# backplane.net
KiCad netlist of a schematic drawn in EAGLE
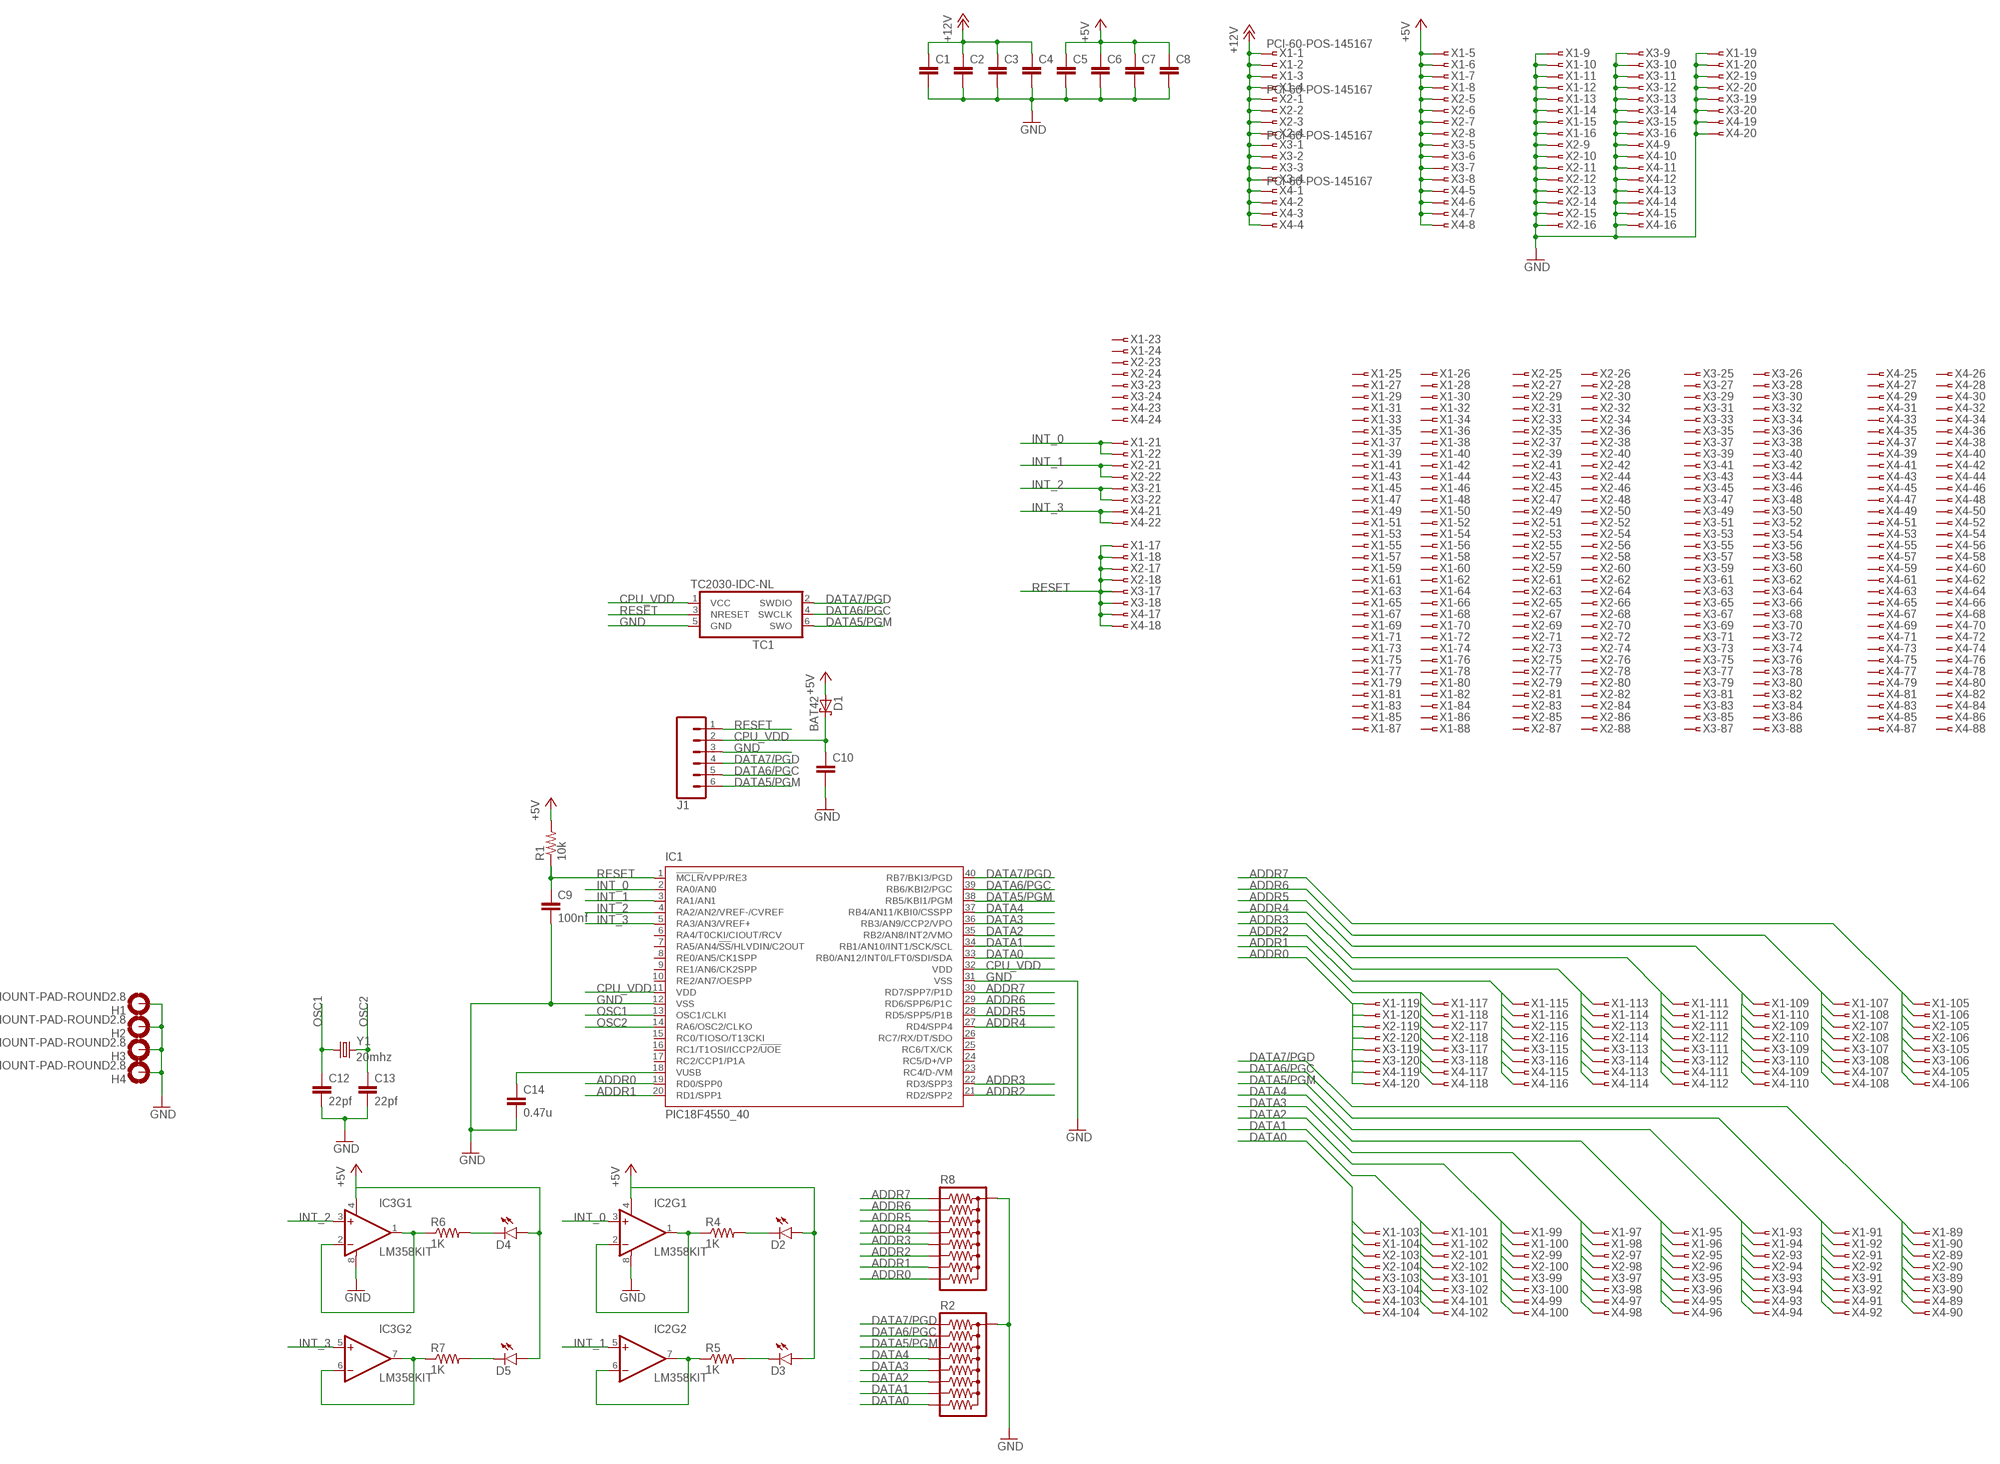
[diagram p0: schematic, sheet 1]

(export (version "E")
  (design (tool "Eeschema 10.0.6"))
  (components
    (comp (ref "C1")
      (value "0.1UF-50V-20%(PTH)KIT-EZ")
      (footprint "eagle-import:CAP-PTH-SMALL-KIT")
      (libsource (lib "eagle-import") (part "0.1UF-50V-20%(PTH)KIT-EZ"))
    )
    (comp (ref "C2")
      (value "0.1UF-50V-20%(PTH)KIT-EZ")
      (footprint "eagle-import:CAP-PTH-SMALL-KIT")
      (libsource (lib "eagle-import") (part "0.1UF-50V-20%(PTH)KIT-EZ"))
    )
    (comp (ref "C3")
      (value "0.1UF-50V-20%(PTH)KIT-EZ")
      (footprint "eagle-import:CAP-PTH-SMALL-KIT")
      (libsource (lib "eagle-import") (part "0.1UF-50V-20%(PTH)KIT-EZ"))
    )
    (comp (ref "C4")
      (value "0.1UF-50V-20%(PTH)KIT-EZ")
      (footprint "eagle-import:CAP-PTH-SMALL-KIT")
      (libsource (lib "eagle-import") (part "0.1UF-50V-20%(PTH)KIT-EZ"))
    )
    (comp (ref "C5")
      (value "0.1UF-50V-20%(PTH)KIT-EZ")
      (footprint "eagle-import:CAP-PTH-SMALL-KIT")
      (libsource (lib "eagle-import") (part "0.1UF-50V-20%(PTH)KIT-EZ"))
    )
    (comp (ref "C6")
      (value "0.1UF-50V-20%(PTH)KIT-EZ")
      (footprint "eagle-import:CAP-PTH-SMALL-KIT")
      (libsource (lib "eagle-import") (part "0.1UF-50V-20%(PTH)KIT-EZ"))
    )
    (comp (ref "C7")
      (value "0.1UF-50V-20%(PTH)KIT-EZ")
      (footprint "eagle-import:CAP-PTH-SMALL-KIT")
      (libsource (lib "eagle-import") (part "0.1UF-50V-20%(PTH)KIT-EZ"))
    )
    (comp (ref "C8")
      (value "0.1UF-50V-20%(PTH)KIT-EZ")
      (footprint "eagle-import:CAP-PTH-SMALL-KIT")
      (libsource (lib "eagle-import") (part "0.1UF-50V-20%(PTH)KIT-EZ"))
    )
    (comp (ref "C9")
      (value "100nf")
      (footprint "eagle-import:CAP-PTH-SMALL-KIT")
      (libsource (lib "eagle-import") (part "0.1UF-50V-20%(PTH)KIT-EZ"))
    )
    (comp (ref "C10")
      (value "0.1UF-50V-20%(PTH)KIT-EZ")
      (footprint "eagle-import:CAP-PTH-SMALL-KIT")
      (libsource (lib "eagle-import") (part "0.1UF-50V-20%(PTH)KIT-EZ"))
    )
    (comp (ref "C12")
      (value "22pf")
      (footprint "eagle-import:CAP-PTH-SMALL-KIT")
      (libsource (lib "eagle-import") (part "CAPKIT"))
    )
    (comp (ref "C13")
      (value "22pf")
      (footprint "eagle-import:CAP-PTH-SMALL-KIT")
      (libsource (lib "eagle-import") (part "CAPKIT"))
    )
    (comp (ref "C14")
      (value "0.47u")
      (footprint "eagle-import:CAP-PTH-SMALL-KIT")
      (libsource (lib "eagle-import") (part "CAPKIT"))
    )
    (comp (ref "D1")
      (value "BAT42")
      (footprint "eagle-import:DO35-10")
      (libsource (lib "eagle-import") (part "BAT42"))
    )
    (comp (ref "D2")
      (value "LED3MM")
      (footprint "eagle-import:LED3MM")
      (libsource (lib "eagle-import") (part "LED3MM"))
    )
    (comp (ref "D3")
      (value "LED3MM")
      (footprint "eagle-import:LED3MM")
      (libsource (lib "eagle-import") (part "LED3MM"))
    )
    (comp (ref "D4")
      (value "LED3MM")
      (footprint "eagle-import:LED3MM")
      (libsource (lib "eagle-import") (part "LED3MM"))
    )
    (comp (ref "D5")
      (value "LED3MM")
      (footprint "eagle-import:LED3MM")
      (libsource (lib "eagle-import") (part "LED3MM"))
    )
    (comp (ref "H1")
      (value "MOUNT-PAD-ROUND2.8")
      (footprint "eagle-import:2,8-PAD")
      (libsource (lib "eagle-import") (part "MOUNT-PAD-ROUND2.8"))
    )
    (comp (ref "H2")
      (value "MOUNT-PAD-ROUND2.8")
      (footprint "eagle-import:2,8-PAD")
      (libsource (lib "eagle-import") (part "MOUNT-PAD-ROUND2.8"))
    )
    (comp (ref "H3")
      (value "MOUNT-PAD-ROUND2.8")
      (footprint "eagle-import:2,8-PAD")
      (libsource (lib "eagle-import") (part "MOUNT-PAD-ROUND2.8"))
    )
    (comp (ref "H4")
      (value "MOUNT-PAD-ROUND2.8")
      (footprint "eagle-import:2,8-PAD")
      (libsource (lib "eagle-import") (part "MOUNT-PAD-ROUND2.8"))
    )
    (comp (ref "IC1")
      (value "PIC18F4550_40")
      (footprint "eagle-import:DIL40")
      (fields (field (name "MF") "MICROCHIP") (field (name "MPN") "PIC18F4550-I/P"))
      (libsource (lib "eagle-import") (part "PIC18F4_40550"))
    )
    (comp (ref "IC2")
      (value "LM358KIT")
      (footprint "eagle-import:DIP08-KIT")
      (libsource (lib "eagle-import") (part "LM358KIT"))
    )
    (comp (ref "IC3")
      (value "LM358KIT")
      (footprint "eagle-import:DIP08-KIT")
      (libsource (lib "eagle-import") (part "LM358KIT"))
    )
    (comp (ref "J1")
      (value "M06POLAR_LOCK")
      (footprint "eagle-import:MOLEX-1X6_LOCK")
      (libsource (lib "eagle-import") (part "M06POLAR_LOCK"))
    )
    (comp (ref "R1")
      (value "10k")
      (footprint "eagle-import:AXIAL-0.3EZ")
      (libsource (lib "eagle-import") (part "10KOHM-1/4W-1%(PTH)HORIZ-KIT"))
    )
    (comp (ref "R2")
      (value "RPACK-BUSSED-8-SIP-PTH-8")
      (footprint "eagle-import:RPACK-SIP-PTH-8")
      (libsource (lib "eagle-import") (part "RPACK-BUSSED-8-SIP-PTH-8"))
    )
    (comp (ref "R4")
      (value "1K")
      (footprint "eagle-import:AXIAL-0.1EZ")
      (libsource (lib "eagle-import") (part "1KOHM-1/4W-1%(PTH)VERT-KIT"))
    )
    (comp (ref "R5")
      (value "1K")
      (footprint "eagle-import:AXIAL-0.1EZ")
      (libsource (lib "eagle-import") (part "1KOHM-1/4W-1%(PTH)VERT-KIT"))
    )
    (comp (ref "R6")
      (value "1K")
      (footprint "eagle-import:AXIAL-0.1EZ")
      (libsource (lib "eagle-import") (part "1KOHM-1/4W-1%(PTH)VERT-KIT"))
    )
    (comp (ref "R7")
      (value "1K")
      (footprint "eagle-import:AXIAL-0.1EZ")
      (libsource (lib "eagle-import") (part "1KOHM-1/4W-1%(PTH)VERT-KIT"))
    )
    (comp (ref "R8")
      (value "RPACK-BUSSED-8-SIP-PTH-8")
      (footprint "eagle-import:RPACK-SIP-PTH-8")
      (libsource (lib "eagle-import") (part "RPACK-BUSSED-8-SIP-PTH-8"))
    )
    (comp (ref "TC1")
      (value "TC2030-IDC-NL")
      (footprint "eagle-import:TC2030-IDC-NL")
      (libsource (lib "eagle-import") (part "TC2030-IDC-NL"))
    )
    (comp (ref "X1")
      (value "PCI-60-POS-145167")
      (footprint "eagle-import:145167-2")
      (libsource (lib "eagle-import") (part "PCI-60-POS-145167"))
    )
    (comp (ref "X2")
      (value "PCI-60-POS-145167")
      (footprint "eagle-import:145167-2")
      (libsource (lib "eagle-import") (part "PCI-60-POS-145167"))
    )
    (comp (ref "X3")
      (value "PCI-60-POS-145167")
      (footprint "eagle-import:145167-2")
      (libsource (lib "eagle-import") (part "PCI-60-POS-145167"))
    )
    (comp (ref "X4")
      (value "PCI-60-POS-145167")
      (footprint "eagle-import:145167-2")
      (libsource (lib "eagle-import") (part "PCI-60-POS-145167"))
    )
    (comp (ref "Y1")
      (value "20mhz")
      (footprint "eagle-import:HC49U-V")
      (libsource (lib "eagle-import") (part "CRYSTALHC49UV"))
    )
  )
  (nets
    (net (code "1") (name "+5V") (class "Default")
      (node (ref "C5") (pin "1") (pinfunction "1_1") (pintype "passive"))
      (node (ref "C6") (pin "1") (pinfunction "1_1") (pintype "passive"))
      (node (ref "C7") (pin "1") (pinfunction "1_1") (pintype "passive"))
      (node (ref "C8") (pin "1") (pinfunction "1_1") (pintype "passive"))
      (node (ref "D1") (pin "A") (pinfunction "A_A") (pintype "passive"))
      (node (ref "D2") (pin "A") (pinfunction "A_A") (pintype "passive"))
      (node (ref "D3") (pin "A") (pinfunction "A_A") (pintype "passive"))
      (node (ref "D4") (pin "A") (pinfunction "A_A") (pintype "passive"))
      (node (ref "D5") (pin "A") (pinfunction "A_A") (pintype "passive"))
      (node (ref "IC2") (pin "4") (pinfunction "V-_4") (pintype "power_in"))
      (node (ref "IC3") (pin "4") (pinfunction "V-_4") (pintype "power_in"))
      (node (ref "R1") (pin "P$2") (pinfunction "2_P$2") (pintype "passive"))
      (node (ref "X1") (pin "5") (pinfunction "1_5") (pintype "passive"))
      (node (ref "X1") (pin "6") (pinfunction "1_6") (pintype "passive"))
      (node (ref "X1") (pin "7") (pinfunction "1_7") (pintype "passive"))
      (node (ref "X1") (pin "8") (pinfunction "1_8") (pintype "passive"))
      (node (ref "X2") (pin "5") (pinfunction "1_5") (pintype "passive"))
      (node (ref "X2") (pin "6") (pinfunction "1_6") (pintype "passive"))
      (node (ref "X2") (pin "7") (pinfunction "1_7") (pintype "passive"))
      (node (ref "X2") (pin "8") (pinfunction "1_8") (pintype "passive"))
      (node (ref "X3") (pin "5") (pinfunction "1_5") (pintype "passive"))
      (node (ref "X3") (pin "6") (pinfunction "1_6") (pintype "passive"))
      (node (ref "X3") (pin "7") (pinfunction "1_7") (pintype "passive"))
      (node (ref "X3") (pin "8") (pinfunction "1_8") (pintype "passive"))
      (node (ref "X4") (pin "5") (pinfunction "1_5") (pintype "passive"))
      (node (ref "X4") (pin "6") (pinfunction "1_6") (pintype "passive"))
      (node (ref "X4") (pin "7") (pinfunction "1_7") (pintype "passive"))
      (node (ref "X4") (pin "8") (pinfunction "1_8") (pintype "passive"))
    )
    (net (code "2") (name "+12V") (class "Default")
      (node (ref "C1") (pin "1") (pinfunction "1_1") (pintype "passive"))
      (node (ref "C2") (pin "1") (pinfunction "1_1") (pintype "passive"))
      (node (ref "C3") (pin "1") (pinfunction "1_1") (pintype "passive"))
      (node (ref "C4") (pin "1") (pinfunction "1_1") (pintype "passive"))
      (node (ref "X1") (pin "1") (pinfunction "1_1") (pintype "passive"))
      (node (ref "X1") (pin "2") (pinfunction "1_2") (pintype "passive"))
      (node (ref "X1") (pin "3") (pinfunction "1_3") (pintype "passive"))
      (node (ref "X1") (pin "4") (pinfunction "1_4") (pintype "passive"))
      (node (ref "X2") (pin "1") (pinfunction "1_1") (pintype "passive"))
      (node (ref "X2") (pin "2") (pinfunction "1_2") (pintype "passive"))
      (node (ref "X2") (pin "3") (pinfunction "1_3") (pintype "passive"))
      (node (ref "X2") (pin "4") (pinfunction "1_4") (pintype "passive"))
      (node (ref "X3") (pin "1") (pinfunction "1_1") (pintype "passive"))
      (node (ref "X3") (pin "2") (pinfunction "1_2") (pintype "passive"))
      (node (ref "X3") (pin "3") (pinfunction "1_3") (pintype "passive"))
      (node (ref "X3") (pin "4") (pinfunction "1_4") (pintype "passive"))
      (node (ref "X4") (pin "1") (pinfunction "1_1") (pintype "passive"))
      (node (ref "X4") (pin "2") (pinfunction "1_2") (pintype "passive"))
      (node (ref "X4") (pin "3") (pinfunction "1_3") (pintype "passive"))
      (node (ref "X4") (pin "4") (pinfunction "1_4") (pintype "passive"))
    )
    (net (code "3") (name "/ADDR0") (class "Default")
      (node (ref "IC1") (pin "19") (pinfunction "RD0/SPP0_19") (pintype "bidirectional"))
      (node (ref "R8") (pin "P$9") (pinfunction "9_P$9") (pintype "passive"))
      (node (ref "X1") (pin "119") (pinfunction "1_119") (pintype "passive"))
      (node (ref "X1") (pin "120") (pinfunction "1_120") (pintype "passive"))
      (node (ref "X2") (pin "119") (pinfunction "1_119") (pintype "passive"))
      (node (ref "X2") (pin "120") (pinfunction "1_120") (pintype "passive"))
      (node (ref "X3") (pin "119") (pinfunction "1_119") (pintype "passive"))
      (node (ref "X3") (pin "120") (pinfunction "1_120") (pintype "passive"))
      (node (ref "X4") (pin "119") (pinfunction "1_119") (pintype "passive"))
      (node (ref "X4") (pin "120") (pinfunction "1_120") (pintype "passive"))
    )
    (net (code "4") (name "/ADDR1") (class "Default")
      (node (ref "IC1") (pin "20") (pinfunction "RD1/SPP1_20") (pintype "bidirectional"))
      (node (ref "R8") (pin "P$8") (pinfunction "8_P$8") (pintype "passive"))
      (node (ref "X1") (pin "117") (pinfunction "1_117") (pintype "passive"))
      (node (ref "X1") (pin "118") (pinfunction "1_118") (pintype "passive"))
      (node (ref "X2") (pin "117") (pinfunction "1_117") (pintype "passive"))
      (node (ref "X2") (pin "118") (pinfunction "1_118") (pintype "passive"))
      (node (ref "X3") (pin "117") (pinfunction "1_117") (pintype "passive"))
      (node (ref "X3") (pin "118") (pinfunction "1_118") (pintype "passive"))
      (node (ref "X4") (pin "117") (pinfunction "1_117") (pintype "passive"))
      (node (ref "X4") (pin "118") (pinfunction "1_118") (pintype "passive"))
    )
    (net (code "5") (name "/ADDR2") (class "Default")
      (node (ref "IC1") (pin "21") (pinfunction "RD2/SPP2_21") (pintype "bidirectional"))
      (node (ref "R8") (pin "P$7") (pinfunction "7_P$7") (pintype "passive"))
      (node (ref "X1") (pin "115") (pinfunction "1_115") (pintype "passive"))
      (node (ref "X1") (pin "116") (pinfunction "1_116") (pintype "passive"))
      (node (ref "X2") (pin "115") (pinfunction "1_115") (pintype "passive"))
      (node (ref "X2") (pin "116") (pinfunction "1_116") (pintype "passive"))
      (node (ref "X3") (pin "115") (pinfunction "1_115") (pintype "passive"))
      (node (ref "X3") (pin "116") (pinfunction "1_116") (pintype "passive"))
      (node (ref "X4") (pin "115") (pinfunction "1_115") (pintype "passive"))
      (node (ref "X4") (pin "116") (pinfunction "1_116") (pintype "passive"))
    )
    (net (code "6") (name "/ADDR3") (class "Default")
      (node (ref "IC1") (pin "22") (pinfunction "RD3/SPP3_22") (pintype "bidirectional"))
      (node (ref "R8") (pin "P$6") (pinfunction "6_P$6") (pintype "passive"))
      (node (ref "X1") (pin "113") (pinfunction "1_113") (pintype "passive"))
      (node (ref "X1") (pin "114") (pinfunction "1_114") (pintype "passive"))
      (node (ref "X2") (pin "113") (pinfunction "1_113") (pintype "passive"))
      (node (ref "X2") (pin "114") (pinfunction "1_114") (pintype "passive"))
      (node (ref "X3") (pin "113") (pinfunction "1_113") (pintype "passive"))
      (node (ref "X3") (pin "114") (pinfunction "1_114") (pintype "passive"))
      (node (ref "X4") (pin "113") (pinfunction "1_113") (pintype "passive"))
      (node (ref "X4") (pin "114") (pinfunction "1_114") (pintype "passive"))
    )
    (net (code "7") (name "/ADDR4") (class "Default")
      (node (ref "IC1") (pin "27") (pinfunction "RD4/SPP4_27") (pintype "bidirectional"))
      (node (ref "R8") (pin "P$5") (pinfunction "5_P$5") (pintype "passive"))
      (node (ref "X1") (pin "111") (pinfunction "1_111") (pintype "passive"))
      (node (ref "X1") (pin "112") (pinfunction "1_112") (pintype "passive"))
      (node (ref "X2") (pin "111") (pinfunction "1_111") (pintype "passive"))
      (node (ref "X2") (pin "112") (pinfunction "1_112") (pintype "passive"))
      (node (ref "X3") (pin "111") (pinfunction "1_111") (pintype "passive"))
      (node (ref "X3") (pin "112") (pinfunction "1_112") (pintype "passive"))
      (node (ref "X4") (pin "111") (pinfunction "1_111") (pintype "passive"))
      (node (ref "X4") (pin "112") (pinfunction "1_112") (pintype "passive"))
    )
    (net (code "8") (name "/ADDR5") (class "Default")
      (node (ref "IC1") (pin "28") (pinfunction "RD5/SPP5/P1B_28") (pintype "bidirectional"))
      (node (ref "R8") (pin "P$4") (pinfunction "4_P$4") (pintype "passive"))
      (node (ref "X1") (pin "109") (pinfunction "1_109") (pintype "passive"))
      (node (ref "X1") (pin "110") (pinfunction "1_110") (pintype "passive"))
      (node (ref "X2") (pin "109") (pinfunction "1_109") (pintype "passive"))
      (node (ref "X2") (pin "110") (pinfunction "1_110") (pintype "passive"))
      (node (ref "X3") (pin "109") (pinfunction "1_109") (pintype "passive"))
      (node (ref "X3") (pin "110") (pinfunction "1_110") (pintype "passive"))
      (node (ref "X4") (pin "109") (pinfunction "1_109") (pintype "passive"))
      (node (ref "X4") (pin "110") (pinfunction "1_110") (pintype "passive"))
    )
    (net (code "9") (name "/ADDR6") (class "Default")
      (node (ref "IC1") (pin "29") (pinfunction "RD6/SPP6/P1C_29") (pintype "bidirectional"))
      (node (ref "R8") (pin "P$3") (pinfunction "3_P$3") (pintype "passive"))
      (node (ref "X1") (pin "107") (pinfunction "1_107") (pintype "passive"))
      (node (ref "X1") (pin "108") (pinfunction "1_108") (pintype "passive"))
      (node (ref "X2") (pin "107") (pinfunction "1_107") (pintype "passive"))
      (node (ref "X2") (pin "108") (pinfunction "1_108") (pintype "passive"))
      (node (ref "X3") (pin "107") (pinfunction "1_107") (pintype "passive"))
      (node (ref "X3") (pin "108") (pinfunction "1_108") (pintype "passive"))
      (node (ref "X4") (pin "107") (pinfunction "1_107") (pintype "passive"))
      (node (ref "X4") (pin "108") (pinfunction "1_108") (pintype "passive"))
    )
    (net (code "10") (name "/ADDR7") (class "Default")
      (node (ref "IC1") (pin "30") (pinfunction "RD7/SPP7/P1D_30") (pintype "bidirectional"))
      (node (ref "R8") (pin "P$2") (pinfunction "2_P$2") (pintype "passive"))
      (node (ref "X1") (pin "105") (pinfunction "1_105") (pintype "passive"))
      (node (ref "X1") (pin "106") (pinfunction "1_106") (pintype "passive"))
      (node (ref "X2") (pin "105") (pinfunction "1_105") (pintype "passive"))
      (node (ref "X2") (pin "106") (pinfunction "1_106") (pintype "passive"))
      (node (ref "X3") (pin "105") (pinfunction "1_105") (pintype "passive"))
      (node (ref "X3") (pin "106") (pinfunction "1_106") (pintype "passive"))
      (node (ref "X4") (pin "105") (pinfunction "1_105") (pintype "passive"))
      (node (ref "X4") (pin "106") (pinfunction "1_106") (pintype "passive"))
    )
    (net (code "11") (name "/CPU_VDD") (class "Default")
      (node (ref "C10") (pin "1") (pinfunction "1_1") (pintype "passive"))
      (node (ref "D1") (pin "C") (pinfunction "C_C") (pintype "passive"))
      (node (ref "IC1") (pin "11") (pinfunction "VDD_11") (pintype "power_in"))
      (node (ref "IC1") (pin "32") (pinfunction "VDD_32") (pintype "power_in"))
      (node (ref "J1") (pin "2") (pinfunction "2_2") (pintype "passive"))
      (node (ref "TC1") (pin "1") (pinfunction "VCC_1") (pintype "passive"))
    )
    (net (code "12") (name "/DATA0") (class "Default")
      (node (ref "IC1") (pin "33") (pinfunction "RB0/AN12/INT0/LFT0/SDI/SDA_33") (pintype "bidirectional"))
      (node (ref "R2") (pin "P$9") (pinfunction "9_P$9") (pintype "passive"))
      (node (ref "X1") (pin "103") (pinfunction "1_103") (pintype "passive"))
      (node (ref "X1") (pin "104") (pinfunction "1_104") (pintype "passive"))
      (node (ref "X2") (pin "103") (pinfunction "1_103") (pintype "passive"))
      (node (ref "X2") (pin "104") (pinfunction "1_104") (pintype "passive"))
      (node (ref "X3") (pin "103") (pinfunction "1_103") (pintype "passive"))
      (node (ref "X3") (pin "104") (pinfunction "1_104") (pintype "passive"))
      (node (ref "X4") (pin "103") (pinfunction "1_103") (pintype "passive"))
      (node (ref "X4") (pin "104") (pinfunction "1_104") (pintype "passive"))
    )
    (net (code "13") (name "/DATA1") (class "Default")
      (node (ref "IC1") (pin "34") (pinfunction "RB1/AN10/INT1/SCK/SCL_34") (pintype "bidirectional"))
      (node (ref "R2") (pin "P$8") (pinfunction "8_P$8") (pintype "passive"))
      (node (ref "X1") (pin "101") (pinfunction "1_101") (pintype "passive"))
      (node (ref "X1") (pin "102") (pinfunction "1_102") (pintype "passive"))
      (node (ref "X2") (pin "101") (pinfunction "1_101") (pintype "passive"))
      (node (ref "X2") (pin "102") (pinfunction "1_102") (pintype "passive"))
      (node (ref "X3") (pin "101") (pinfunction "1_101") (pintype "passive"))
      (node (ref "X3") (pin "102") (pinfunction "1_102") (pintype "passive"))
      (node (ref "X4") (pin "101") (pinfunction "1_101") (pintype "passive"))
      (node (ref "X4") (pin "102") (pinfunction "1_102") (pintype "passive"))
    )
    (net (code "14") (name "/DATA2") (class "Default")
      (node (ref "IC1") (pin "35") (pinfunction "RB2/AN8/INT2/VMO_35") (pintype "bidirectional"))
      (node (ref "R2") (pin "P$7") (pinfunction "7_P$7") (pintype "passive"))
      (node (ref "X1") (pin "100") (pinfunction "1_100") (pintype "passive"))
      (node (ref "X1") (pin "99") (pinfunction "1_99") (pintype "passive"))
      (node (ref "X2") (pin "100") (pinfunction "1_100") (pintype "passive"))
      (node (ref "X2") (pin "99") (pinfunction "1_99") (pintype "passive"))
      (node (ref "X3") (pin "100") (pinfunction "1_100") (pintype "passive"))
      (node (ref "X3") (pin "99") (pinfunction "1_99") (pintype "passive"))
      (node (ref "X4") (pin "100") (pinfunction "1_100") (pintype "passive"))
      (node (ref "X4") (pin "99") (pinfunction "1_99") (pintype "passive"))
    )
    (net (code "15") (name "/DATA3") (class "Default")
      (node (ref "IC1") (pin "36") (pinfunction "RB3/AN9/CCP2/VPO_36") (pintype "bidirectional"))
      (node (ref "R2") (pin "P$6") (pinfunction "6_P$6") (pintype "passive"))
      (node (ref "X1") (pin "97") (pinfunction "1_97") (pintype "passive"))
      (node (ref "X1") (pin "98") (pinfunction "1_98") (pintype "passive"))
      (node (ref "X2") (pin "97") (pinfunction "1_97") (pintype "passive"))
      (node (ref "X2") (pin "98") (pinfunction "1_98") (pintype "passive"))
      (node (ref "X3") (pin "97") (pinfunction "1_97") (pintype "passive"))
      (node (ref "X3") (pin "98") (pinfunction "1_98") (pintype "passive"))
      (node (ref "X4") (pin "97") (pinfunction "1_97") (pintype "passive"))
      (node (ref "X4") (pin "98") (pinfunction "1_98") (pintype "passive"))
    )
    (net (code "16") (name "/DATA4") (class "Default")
      (node (ref "IC1") (pin "37") (pinfunction "RB4/AN11/KBI0/CSSPP_37") (pintype "bidirectional"))
      (node (ref "R2") (pin "P$5") (pinfunction "5_P$5") (pintype "passive"))
      (node (ref "X1") (pin "95") (pinfunction "1_95") (pintype "passive"))
      (node (ref "X1") (pin "96") (pinfunction "1_96") (pintype "passive"))
      (node (ref "X2") (pin "95") (pinfunction "1_95") (pintype "passive"))
      (node (ref "X2") (pin "96") (pinfunction "1_96") (pintype "passive"))
      (node (ref "X3") (pin "95") (pinfunction "1_95") (pintype "passive"))
      (node (ref "X3") (pin "96") (pinfunction "1_96") (pintype "passive"))
      (node (ref "X4") (pin "95") (pinfunction "1_95") (pintype "passive"))
      (node (ref "X4") (pin "96") (pinfunction "1_96") (pintype "passive"))
    )
    (net (code "17") (name "/DATA5{slash}PGM") (class "Default")
      (node (ref "IC1") (pin "38") (pinfunction "RB5/KBI1/PGM_38") (pintype "bidirectional"))
      (node (ref "J1") (pin "6") (pinfunction "6_6") (pintype "passive"))
      (node (ref "R2") (pin "P$4") (pinfunction "4_P$4") (pintype "passive"))
      (node (ref "TC1") (pin "6") (pinfunction "SWO_6") (pintype "passive"))
      (node (ref "X1") (pin "93") (pinfunction "1_93") (pintype "passive"))
      (node (ref "X1") (pin "94") (pinfunction "1_94") (pintype "passive"))
      (node (ref "X2") (pin "93") (pinfunction "1_93") (pintype "passive"))
      (node (ref "X2") (pin "94") (pinfunction "1_94") (pintype "passive"))
      (node (ref "X3") (pin "93") (pinfunction "1_93") (pintype "passive"))
      (node (ref "X3") (pin "94") (pinfunction "1_94") (pintype "passive"))
      (node (ref "X4") (pin "93") (pinfunction "1_93") (pintype "passive"))
      (node (ref "X4") (pin "94") (pinfunction "1_94") (pintype "passive"))
    )
    (net (code "18") (name "/DATA6{slash}PGC") (class "Default")
      (node (ref "IC1") (pin "39") (pinfunction "RB6/KBI2/PGC_39") (pintype "bidirectional"))
      (node (ref "J1") (pin "5") (pinfunction "5_5") (pintype "passive"))
      (node (ref "R2") (pin "P$3") (pinfunction "3_P$3") (pintype "passive"))
      (node (ref "TC1") (pin "4") (pinfunction "SWCLK_4") (pintype "passive"))
      (node (ref "X1") (pin "91") (pinfunction "1_91") (pintype "passive"))
      (node (ref "X1") (pin "92") (pinfunction "1_92") (pintype "passive"))
      (node (ref "X2") (pin "91") (pinfunction "1_91") (pintype "passive"))
      (node (ref "X2") (pin "92") (pinfunction "1_92") (pintype "passive"))
      (node (ref "X3") (pin "91") (pinfunction "1_91") (pintype "passive"))
      (node (ref "X3") (pin "92") (pinfunction "1_92") (pintype "passive"))
      (node (ref "X4") (pin "91") (pinfunction "1_91") (pintype "passive"))
      (node (ref "X4") (pin "92") (pinfunction "1_92") (pintype "passive"))
    )
    (net (code "19") (name "/DATA7{slash}PGD") (class "Default")
      (node (ref "IC1") (pin "40") (pinfunction "RB7/BKI3/PGD_40") (pintype "bidirectional"))
      (node (ref "J1") (pin "4") (pinfunction "4_4") (pintype "passive"))
      (node (ref "R2") (pin "P$2") (pinfunction "2_P$2") (pintype "passive"))
      (node (ref "TC1") (pin "2") (pinfunction "SWDIO_2") (pintype "passive"))
      (node (ref "X1") (pin "89") (pinfunction "1_89") (pintype "passive"))
      (node (ref "X1") (pin "90") (pinfunction "1_90") (pintype "passive"))
      (node (ref "X2") (pin "89") (pinfunction "1_89") (pintype "passive"))
      (node (ref "X2") (pin "90") (pinfunction "1_90") (pintype "passive"))
      (node (ref "X3") (pin "89") (pinfunction "1_89") (pintype "passive"))
      (node (ref "X3") (pin "90") (pinfunction "1_90") (pintype "passive"))
      (node (ref "X4") (pin "89") (pinfunction "1_89") (pintype "passive"))
      (node (ref "X4") (pin "90") (pinfunction "1_90") (pintype "passive"))
    )
    (net (code "20") (name "/INT_0") (class "Default")
      (node (ref "IC1") (pin "2") (pinfunction "RA0/AN0_2") (pintype "bidirectional"))
      (node (ref "IC2") (pin "3") (pinfunction "+IN_3") (pintype "input"))
      (node (ref "X1") (pin "21") (pinfunction "1_21") (pintype "passive"))
      (node (ref "X1") (pin "22") (pinfunction "1_22") (pintype "passive"))
    )
    (net (code "21") (name "/INT_1") (class "Default")
      (node (ref "IC1") (pin "3") (pinfunction "RA1/AN1_3") (pintype "bidirectional"))
      (node (ref "IC2") (pin "5") (pinfunction "+IN_5") (pintype "input"))
      (node (ref "X2") (pin "21") (pinfunction "1_21") (pintype "passive"))
      (node (ref "X2") (pin "22") (pinfunction "1_22") (pintype "passive"))
    )
    (net (code "22") (name "/INT_2") (class "Default")
      (node (ref "IC1") (pin "4") (pinfunction "RA2/AN2/VREF-/CVREF_4") (pintype "bidirectional"))
      (node (ref "IC3") (pin "3") (pinfunction "+IN_3") (pintype "input"))
      (node (ref "X3") (pin "21") (pinfunction "1_21") (pintype "passive"))
      (node (ref "X3") (pin "22") (pinfunction "1_22") (pintype "passive"))
    )
    (net (code "23") (name "/INT_3") (class "Default")
      (node (ref "IC1") (pin "5") (pinfunction "RA3/AN3/VREF+_5") (pintype "bidirectional"))
      (node (ref "IC3") (pin "5") (pinfunction "+IN_5") (pintype "input"))
      (node (ref "X4") (pin "21") (pinfunction "1_21") (pintype "passive"))
      (node (ref "X4") (pin "22") (pinfunction "1_22") (pintype "passive"))
    )
    (net (code "24") (name "/OSC1") (class "Default")
      (node (ref "C12") (pin "1") (pinfunction "1_1") (pintype "passive"))
      (node (ref "IC1") (pin "13") (pinfunction "OSC1/CLKI_13") (pintype "input"))
      (node (ref "Y1") (pin "1") (pinfunction "1_1") (pintype "passive"))
    )
    (net (code "25") (name "/OSC2") (class "Default")
      (node (ref "C13") (pin "1") (pinfunction "1_1") (pintype "passive"))
      (node (ref "IC1") (pin "14") (pinfunction "RA6/OSC2/CLKO_14") (pintype "output"))
      (node (ref "Y1") (pin "2") (pinfunction "2_2") (pintype "passive"))
    )
    (net (code "26") (name "/RESET") (class "Default")
      (node (ref "C9") (pin "1") (pinfunction "1_1") (pintype "passive"))
      (node (ref "IC1") (pin "1") (pinfunction "~{MCLR}/VPP/RE3_1") (pintype "input"))
      (node (ref "J1") (pin "1") (pinfunction "1_1") (pintype "passive"))
      (node (ref "R1") (pin "P$1") (pinfunction "1_P$1") (pintype "passive"))
      (node (ref "TC1") (pin "3") (pinfunction "NRESET_3") (pintype "passive"))
      (node (ref "X1") (pin "17") (pinfunction "1_17") (pintype "passive"))
      (node (ref "X1") (pin "18") (pinfunction "1_18") (pintype "passive"))
      (node (ref "X2") (pin "17") (pinfunction "1_17") (pintype "passive"))
      (node (ref "X2") (pin "18") (pinfunction "1_18") (pintype "passive"))
      (node (ref "X3") (pin "17") (pinfunction "1_17") (pintype "passive"))
      (node (ref "X3") (pin "18") (pinfunction "1_18") (pintype "passive"))
      (node (ref "X4") (pin "17") (pinfunction "1_17") (pintype "passive"))
      (node (ref "X4") (pin "18") (pinfunction "1_18") (pintype "passive"))
    )
    (net (code "27") (name "GND") (class "Default")
      (node (ref "C1") (pin "2") (pinfunction "2_2") (pintype "passive"))
      (node (ref "C10") (pin "2") (pinfunction "2_2") (pintype "passive"))
      (node (ref "C12") (pin "2") (pinfunction "2_2") (pintype "passive"))
      (node (ref "C13") (pin "2") (pinfunction "2_2") (pintype "passive"))
      (node (ref "C14") (pin "2") (pinfunction "2_2") (pintype "passive"))
      (node (ref "C2") (pin "2") (pinfunction "2_2") (pintype "passive"))
      (node (ref "C3") (pin "2") (pinfunction "2_2") (pintype "passive"))
      (node (ref "C4") (pin "2") (pinfunction "2_2") (pintype "passive"))
      (node (ref "C5") (pin "2") (pinfunction "2_2") (pintype "passive"))
      (node (ref "C6") (pin "2") (pinfunction "2_2") (pintype "passive"))
      (node (ref "C7") (pin "2") (pinfunction "2_2") (pintype "passive"))
      (node (ref "C8") (pin "2") (pinfunction "2_2") (pintype "passive"))
      (node (ref "C9") (pin "2") (pinfunction "2_2") (pintype "passive"))
      (node (ref "H1") (pin "B2,8") (pinfunction "MOUNT_B2,8") (pintype "passive"))
      (node (ref "H2") (pin "B2,8") (pinfunction "MOUNT_B2,8") (pintype "passive"))
      (node (ref "H3") (pin "B2,8") (pinfunction "MOUNT_B2,8") (pintype "passive"))
      (node (ref "H4") (pin "B2,8") (pinfunction "MOUNT_B2,8") (pintype "passive"))
      (node (ref "IC1") (pin "12") (pinfunction "VSS_12") (pintype "power_in"))
      (node (ref "IC1") (pin "31") (pinfunction "VSS_31") (pintype "power_in"))
      (node (ref "IC2") (pin "8") (pinfunction "V+_8") (pintype "power_in"))
      (node (ref "IC3") (pin "8") (pinfunction "V+_8") (pintype "power_in"))
      (node (ref "J1") (pin "3") (pinfunction "3_3") (pintype "passive"))
      (node (ref "R2") (pin "P$1") (pinfunction "1_P$1") (pintype "passive"))
      (node (ref "R8") (pin "P$1") (pinfunction "1_P$1") (pintype "passive"))
      (node (ref "TC1") (pin "5") (pinfunction "GND_5") (pintype "passive"))
      (node (ref "X1") (pin "10") (pinfunction "1_10") (pintype "passive"))
      (node (ref "X1") (pin "11") (pinfunction "1_11") (pintype "passive"))
      (node (ref "X1") (pin "12") (pinfunction "1_12") (pintype "passive"))
      (node (ref "X1") (pin "13") (pinfunction "1_13") (pintype "passive"))
      (node (ref "X1") (pin "14") (pinfunction "1_14") (pintype "passive"))
      (node (ref "X1") (pin "15") (pinfunction "1_15") (pintype "passive"))
      (node (ref "X1") (pin "16") (pinfunction "1_16") (pintype "passive"))
      (node (ref "X1") (pin "19") (pinfunction "1_19") (pintype "passive"))
      (node (ref "X1") (pin "20") (pinfunction "1_20") (pintype "passive"))
      (node (ref "X1") (pin "9") (pinfunction "1_9") (pintype "passive"))
      (node (ref "X2") (pin "10") (pinfunction "1_10") (pintype "passive"))
      (node (ref "X2") (pin "11") (pinfunction "1_11") (pintype "passive"))
      (node (ref "X2") (pin "12") (pinfunction "1_12") (pintype "passive"))
      (node (ref "X2") (pin "13") (pinfunction "1_13") (pintype "passive"))
      (node (ref "X2") (pin "14") (pinfunction "1_14") (pintype "passive"))
      (node (ref "X2") (pin "15") (pinfunction "1_15") (pintype "passive"))
      (node (ref "X2") (pin "16") (pinfunction "1_16") (pintype "passive"))
      (node (ref "X2") (pin "19") (pinfunction "1_19") (pintype "passive"))
      (node (ref "X2") (pin "20") (pinfunction "1_20") (pintype "passive"))
      (node (ref "X2") (pin "9") (pinfunction "1_9") (pintype "passive"))
      (node (ref "X3") (pin "10") (pinfunction "1_10") (pintype "passive"))
      (node (ref "X3") (pin "11") (pinfunction "1_11") (pintype "passive"))
      (node (ref "X3") (pin "12") (pinfunction "1_12") (pintype "passive"))
      (node (ref "X3") (pin "13") (pinfunction "1_13") (pintype "passive"))
      (node (ref "X3") (pin "14") (pinfunction "1_14") (pintype "passive"))
      (node (ref "X3") (pin "15") (pinfunction "1_15") (pintype "passive"))
      (node (ref "X3") (pin "16") (pinfunction "1_16") (pintype "passive"))
      (node (ref "X3") (pin "19") (pinfunction "1_19") (pintype "passive"))
      (node (ref "X3") (pin "20") (pinfunction "1_20") (pintype "passive"))
      (node (ref "X3") (pin "9") (pinfunction "1_9") (pintype "passive"))
      (node (ref "X4") (pin "10") (pinfunction "1_10") (pintype "passive"))
      (node (ref "X4") (pin "11") (pinfunction "1_11") (pintype "passive"))
      (node (ref "X4") (pin "12") (pinfunction "1_12") (pintype "passive"))
      (node (ref "X4") (pin "13") (pinfunction "1_13") (pintype "passive"))
      (node (ref "X4") (pin "14") (pinfunction "1_14") (pintype "passive"))
      (node (ref "X4") (pin "15") (pinfunction "1_15") (pintype "passive"))
      (node (ref "X4") (pin "16") (pinfunction "1_16") (pintype "passive"))
      (node (ref "X4") (pin "19") (pinfunction "1_19") (pintype "passive"))
      (node (ref "X4") (pin "20") (pinfunction "1_20") (pintype "passive"))
      (node (ref "X4") (pin "9") (pinfunction "1_9") (pintype "passive"))
    )
    (net (code "28") (name "Net-(D2-C)") (class "Default")
      (node (ref "D2") (pin "K") (pinfunction "C_K") (pintype "passive"))
      (node (ref "R4") (pin "P$2") (pinfunction "2_P$2") (pintype "passive"))
    )
    (net (code "29") (name "Net-(D3-C)") (class "Default")
      (node (ref "D3") (pin "K") (pinfunction "C_K") (pintype "passive"))
      (node (ref "R5") (pin "P$2") (pinfunction "2_P$2") (pintype "passive"))
    )
    (net (code "30") (name "Net-(D4-C)") (class "Default")
      (node (ref "D4") (pin "K") (pinfunction "C_K") (pintype "passive"))
      (node (ref "R6") (pin "P$2") (pinfunction "2_P$2") (pintype "passive"))
    )
    (net (code "31") (name "Net-(D5-C)") (class "Default")
      (node (ref "D5") (pin "K") (pinfunction "C_K") (pintype "passive"))
      (node (ref "R7") (pin "P$2") (pinfunction "2_P$2") (pintype "passive"))
    )
    (net (code "32") (name "Net-(IC1-VUSB)") (class "Default")
      (node (ref "C14") (pin "1") (pinfunction "1_1") (pintype "passive"))
      (node (ref "IC1") (pin "18") (pinfunction "VUSB_18") (pintype "bidirectional"))
    )
    (net (code "33") (name "Net-(IC2A--IN)") (class "Default")
      (node (ref "IC2") (pin "1") (pinfunction "OUT_1") (pintype "output"))
      (node (ref "IC2") (pin "2") (pinfunction "-IN_2") (pintype "input"))
      (node (ref "R4") (pin "P$1") (pinfunction "1_P$1") (pintype "passive"))
    )
    (net (code "34") (name "Net-(IC2B--IN)") (class "Default")
      (node (ref "IC2") (pin "6") (pinfunction "-IN_6") (pintype "input"))
      (node (ref "IC2") (pin "7") (pinfunction "OUT_7") (pintype "output"))
      (node (ref "R5") (pin "P$1") (pinfunction "1_P$1") (pintype "passive"))
    )
    (net (code "35") (name "Net-(IC3A--IN)") (class "Default")
      (node (ref "IC3") (pin "1") (pinfunction "OUT_1") (pintype "output"))
      (node (ref "IC3") (pin "2") (pinfunction "-IN_2") (pintype "input"))
      (node (ref "R6") (pin "P$1") (pinfunction "1_P$1") (pintype "passive"))
    )
    (net (code "36") (name "Net-(IC3B--IN)") (class "Default")
      (node (ref "IC3") (pin "6") (pinfunction "-IN_6") (pintype "input"))
      (node (ref "IC3") (pin "7") (pinfunction "OUT_7") (pintype "output"))
      (node (ref "R7") (pin "P$1") (pinfunction "1_P$1") (pintype "passive"))
    )
    (net (code "37") (name "unconnected-(IC1-RA4{slash}T0CKI{slash}CIOUT{slash}RCV-Pad6)") (class "Default")
      (node (ref "IC1") (pin "6") (pinfunction "RA4/T0CKI/CIOUT/RCV_6") (pintype "bidirectional"))
    )
    (net (code "38") (name "unconnected-(IC1-RA5{slash}AN4{slash}~{SS}{slash}HLVDIN{slash}C2OUT-Pad7)") (class "Default")
      (node (ref "IC1") (pin "7") (pinfunction "RA5/AN4/~{SS}/HLVDIN/C2OUT_7") (pintype "bidirectional"))
    )
    (net (code "39") (name "unconnected-(IC1-RC0{slash}TIOSO{slash}T13CKI-Pad15)") (class "Default")
      (node (ref "IC1") (pin "15") (pinfunction "RC0/TIOSO/T13CKI_15") (pintype "bidirectional"))
    )
    (net (code "40") (name "unconnected-(IC1-RC1{slash}T1OSI{slash}ICCP2{slash}~{UOE}-Pad16)") (class "Default")
      (node (ref "IC1") (pin "16") (pinfunction "RC1/T1OSI/ICCP2/~{UOE}_16") (pintype "bidirectional"))
    )
    (net (code "41") (name "unconnected-(IC1-RC2{slash}CCP1{slash}P1A-Pad17)") (class "Default")
      (node (ref "IC1") (pin "17") (pinfunction "RC2/CCP1/P1A_17") (pintype "bidirectional"))
    )
    (net (code "42") (name "unconnected-(IC1-RC4{slash}D-{slash}VM-Pad23)") (class "Default")
      (node (ref "IC1") (pin "23") (pinfunction "RC4/D-/VM_23") (pintype "bidirectional"))
    )
    (net (code "43") (name "unconnected-(IC1-RC5{slash}D+{slash}VP-Pad24)") (class "Default")
      (node (ref "IC1") (pin "24") (pinfunction "RC5/D+/VP_24") (pintype "bidirectional"))
    )
    (net (code "44") (name "unconnected-(IC1-RC6{slash}TX{slash}CK-Pad25)") (class "Default")
      (node (ref "IC1") (pin "25") (pinfunction "RC6/TX/CK_25") (pintype "bidirectional"))
    )
    (net (code "45") (name "unconnected-(IC1-RC7{slash}RX{slash}DT{slash}SDO-Pad26)") (class "Default")
      (node (ref "IC1") (pin "26") (pinfunction "RC7/RX/DT/SDO_26") (pintype "bidirectional"))
    )
    (net (code "46") (name "unconnected-(IC1-RE0{slash}AN5{slash}CK1SPP-Pad8)") (class "Default")
      (node (ref "IC1") (pin "8") (pinfunction "RE0/AN5/CK1SPP_8") (pintype "bidirectional"))
    )
    (net (code "47") (name "unconnected-(IC1-RE1{slash}AN6{slash}CK2SPP-Pad9)") (class "Default")
      (node (ref "IC1") (pin "9") (pinfunction "RE1/AN6/CK2SPP_9") (pintype "bidirectional"))
    )
    (net (code "48") (name "unconnected-(IC1-RE2{slash}AN7{slash}OESPP-Pad10)") (class "Default")
      (node (ref "IC1") (pin "10") (pinfunction "RE2/AN7/OESPP_10") (pintype "bidirectional"))
    )
    (net (code "49") (name "unconnected-(X1AK-1-Pad23)") (class "Default")
      (node (ref "X1") (pin "23") (pinfunction "1_23") (pintype "passive"))
    )
    (net (code "50") (name "unconnected-(X1AL-1-Pad24)") (class "Default")
      (node (ref "X1") (pin "24") (pinfunction "1_24") (pintype "passive"))
    )
    (net (code "51") (name "unconnected-(X1AM-1-Pad25)") (class "Default")
      (node (ref "X1") (pin "25") (pinfunction "1_25") (pintype "passive"))
    )
    (net (code "52") (name "unconnected-(X1AN-1-Pad26)") (class "Default")
      (node (ref "X1") (pin "26") (pinfunction "1_26") (pintype "passive"))
    )
    (net (code "53") (name "unconnected-(X1AO-1-Pad27)") (class "Default")
      (node (ref "X1") (pin "27") (pinfunction "1_27") (pintype "passive"))
    )
    (net (code "54") (name "unconnected-(X1AP-1-Pad28)") (class "Default")
      (node (ref "X1") (pin "28") (pinfunction "1_28") (pintype "passive"))
    )
    (net (code "55") (name "unconnected-(X1AQ-1-Pad29)") (class "Default")
      (node (ref "X1") (pin "29") (pinfunction "1_29") (pintype "passive"))
    )
    (net (code "56") (name "unconnected-(X1AS-1-Pad30)") (class "Default")
      (node (ref "X1") (pin "30") (pinfunction "1_30") (pintype "passive"))
    )
    (net (code "57") (name "unconnected-(X1AT-1-Pad31)") (class "Default")
      (node (ref "X1") (pin "31") (pinfunction "1_31") (pintype "passive"))
    )
    (net (code "58") (name "unconnected-(X1AU-1-Pad32)") (class "Default")
      (node (ref "X1") (pin "32") (pinfunction "1_32") (pintype "passive"))
    )
    (net (code "59") (name "unconnected-(X1AV-1-Pad33)") (class "Default")
      (node (ref "X1") (pin "33") (pinfunction "1_33") (pintype "passive"))
    )
    (net (code "60") (name "unconnected-(X1AW-1-Pad34)") (class "Default")
      (node (ref "X1") (pin "34") (pinfunction "1_34") (pintype "passive"))
    )
    (net (code "61") (name "unconnected-(X1AX-1-Pad35)") (class "Default")
      (node (ref "X1") (pin "35") (pinfunction "1_35") (pintype "passive"))
    )
    (net (code "62") (name "unconnected-(X1AY-1-Pad36)") (class "Default")
      (node (ref "X1") (pin "36") (pinfunction "1_36") (pintype "passive"))
    )
    (net (code "63") (name "unconnected-(X1AZ-1-Pad37)") (class "Default")
      (node (ref "X1") (pin "37") (pinfunction "1_37") (pintype "passive"))
    )
    (net (code "64") (name "unconnected-(X1BA-1-Pad38)") (class "Default")
      (node (ref "X1") (pin "38") (pinfunction "1_38") (pintype "passive"))
    )
    (net (code "65") (name "unconnected-(X1BB-1-Pad39)") (class "Default")
      (node (ref "X1") (pin "39") (pinfunction "1_39") (pintype "passive"))
    )
    (net (code "66") (name "unconnected-(X1BD-1-Pad40)") (class "Default")
      (node (ref "X1") (pin "40") (pinfunction "1_40") (pintype "passive"))
    )
    (net (code "67") (name "unconnected-(X1BE-1-Pad41)") (class "Default")
      (node (ref "X1") (pin "41") (pinfunction "1_41") (pintype "passive"))
    )
    (net (code "68") (name "unconnected-(X1BF-1-Pad42)") (class "Default")
      (node (ref "X1") (pin "42") (pinfunction "1_42") (pintype "passive"))
    )
    (net (code "69") (name "unconnected-(X1BG-1-Pad43)") (class "Default")
      (node (ref "X1") (pin "43") (pinfunction "1_43") (pintype "passive"))
    )
    (net (code "70") (name "unconnected-(X1BH-1-Pad44)") (class "Default")
      (node (ref "X1") (pin "44") (pinfunction "1_44") (pintype "passive"))
    )
    (net (code "71") (name "unconnected-(X1BI-1-Pad45)") (class "Default")
      (node (ref "X1") (pin "45") (pinfunction "1_45") (pintype "passive"))
    )
    (net (code "72") (name "unconnected-(X1BJ-1-Pad46)") (class "Default")
      (node (ref "X1") (pin "46") (pinfunction "1_46") (pintype "passive"))
    )
    (net (code "73") (name "unconnected-(X1BK-1-Pad47)") (class "Default")
      (node (ref "X1") (pin "47") (pinfunction "1_47") (pintype "passive"))
    )
    (net (code "74") (name "unconnected-(X1BL-1-Pad48)") (class "Default")
      (node (ref "X1") (pin "48") (pinfunction "1_48") (pintype "passive"))
    )
    (net (code "75") (name "unconnected-(X1BM-1-Pad49)") (class "Default")
      (node (ref "X1") (pin "49") (pinfunction "1_49") (pintype "passive"))
    )
    (net (code "76") (name "unconnected-(X1BO-1-Pad50)") (class "Default")
      (node (ref "X1") (pin "50") (pinfunction "1_50") (pintype "passive"))
    )
    (net (code "77") (name "unconnected-(X1BP-1-Pad51)") (class "Default")
      (node (ref "X1") (pin "51") (pinfunction "1_51") (pintype "passive"))
    )
    (net (code "78") (name "unconnected-(X1BQ-1-Pad52)") (class "Default")
      (node (ref "X1") (pin "52") (pinfunction "1_52") (pintype "passive"))
    )
    (net (code "79") (name "unconnected-(X1BR-1-Pad53)") (class "Default")
      (node (ref "X1") (pin "53") (pinfunction "1_53") (pintype "passive"))
    )
    (net (code "80") (name "unconnected-(X1BS-1-Pad54)") (class "Default")
      (node (ref "X1") (pin "54") (pinfunction "1_54") (pintype "passive"))
    )
    (net (code "81") (name "unconnected-(X1BT-1-Pad55)") (class "Default")
      (node (ref "X1") (pin "55") (pinfunction "1_55") (pintype "passive"))
    )
    (net (code "82") (name "unconnected-(X1BU-1-Pad56)") (class "Default")
      (node (ref "X1") (pin "56") (pinfunction "1_56") (pintype "passive"))
    )
    (net (code "83") (name "unconnected-(X1BV-1-Pad57)") (class "Default")
      (node (ref "X1") (pin "57") (pinfunction "1_57") (pintype "passive"))
    )
    (net (code "84") (name "unconnected-(X1BW-1-Pad58)") (class "Default")
      (node (ref "X1") (pin "58") (pinfunction "1_58") (pintype "passive"))
    )
    (net (code "85") (name "unconnected-(X1BX-1-Pad59)") (class "Default")
      (node (ref "X1") (pin "59") (pinfunction "1_59") (pintype "passive"))
    )
    (net (code "86") (name "unconnected-(X1BZ-1-Pad60)") (class "Default")
      (node (ref "X1") (pin "60") (pinfunction "1_60") (pintype "passive"))
    )
    (net (code "87") (name "unconnected-(X1CA-1-Pad61)") (class "Default")
      (node (ref "X1") (pin "61") (pinfunction "1_61") (pintype "passive"))
    )
    (net (code "88") (name "unconnected-(X1CB-1-Pad62)") (class "Default")
      (node (ref "X1") (pin "62") (pinfunction "1_62") (pintype "passive"))
    )
    (net (code "89") (name "unconnected-(X1CC-1-Pad63)") (class "Default")
      (node (ref "X1") (pin "63") (pinfunction "1_63") (pintype "passive"))
    )
    (net (code "90") (name "unconnected-(X1CD-1-Pad64)") (class "Default")
      (node (ref "X1") (pin "64") (pinfunction "1_64") (pintype "passive"))
    )
    (net (code "91") (name "unconnected-(X1CE-1-Pad65)") (class "Default")
      (node (ref "X1") (pin "65") (pinfunction "1_65") (pintype "passive"))
    )
    (net (code "92") (name "unconnected-(X1CF-1-Pad66)") (class "Default")
      (node (ref "X1") (pin "66") (pinfunction "1_66") (pintype "passive"))
    )
    (net (code "93") (name "unconnected-(X1CG-1-Pad67)") (class "Default")
      (node (ref "X1") (pin "67") (pinfunction "1_67") (pintype "passive"))
    )
    (net (code "94") (name "unconnected-(X1CH-1-Pad68)") (class "Default")
      (node (ref "X1") (pin "68") (pinfunction "1_68") (pintype "passive"))
    )
    (net (code "95") (name "unconnected-(X1CI-1-Pad69)") (class "Default")
      (node (ref "X1") (pin "69") (pinfunction "1_69") (pintype "passive"))
    )
    (net (code "96") (name "unconnected-(X1CK-1-Pad70)") (class "Default")
      (node (ref "X1") (pin "70") (pinfunction "1_70") (pintype "passive"))
    )
    (net (code "97") (name "unconnected-(X1CL-1-Pad71)") (class "Default")
      (node (ref "X1") (pin "71") (pinfunction "1_71") (pintype "passive"))
    )
    (net (code "98") (name "unconnected-(X1CM-1-Pad72)") (class "Default")
      (node (ref "X1") (pin "72") (pinfunction "1_72") (pintype "passive"))
    )
    (net (code "99") (name "unconnected-(X1CN-1-Pad73)") (class "Default")
      (node (ref "X1") (pin "73") (pinfunction "1_73") (pintype "passive"))
    )
    (net (code "100") (name "unconnected-(X1CO-1-Pad74)") (class "Default")
      (node (ref "X1") (pin "74") (pinfunction "1_74") (pintype "passive"))
    )
    (net (code "101") (name "unconnected-(X1CP-1-Pad75)") (class "Default")
      (node (ref "X1") (pin "75") (pinfunction "1_75") (pintype "passive"))
    )
    (net (code "102") (name "unconnected-(X1CQ-1-Pad76)") (class "Default")
      (node (ref "X1") (pin "76") (pinfunction "1_76") (pintype "passive"))
    )
    (net (code "103") (name "unconnected-(X1CR-1-Pad77)") (class "Default")
      (node (ref "X1") (pin "77") (pinfunction "1_77") (pintype "passive"))
    )
    (net (code "104") (name "unconnected-(X1CS-1-Pad78)") (class "Default")
      (node (ref "X1") (pin "78") (pinfunction "1_78") (pintype "passive"))
    )
    (net (code "105") (name "unconnected-(X1CT-1-Pad79)") (class "Default")
      (node (ref "X1") (pin "79") (pinfunction "1_79") (pintype "passive"))
    )
    (net (code "106") (name "unconnected-(X1CV-1-Pad80)") (class "Default")
      (node (ref "X1") (pin "80") (pinfunction "1_80") (pintype "passive"))
    )
    (net (code "107") (name "unconnected-(X1CW-1-Pad81)") (class "Default")
      (node (ref "X1") (pin "81") (pinfunction "1_81") (pintype "passive"))
    )
    (net (code "108") (name "unconnected-(X1CX-1-Pad82)") (class "Default")
      (node (ref "X1") (pin "82") (pinfunction "1_82") (pintype "passive"))
    )
    (net (code "109") (name "unconnected-(X1CY-1-Pad83)") (class "Default")
      (node (ref "X1") (pin "83") (pinfunction "1_83") (pintype "passive"))
    )
    (net (code "110") (name "unconnected-(X1CZ-1-Pad84)") (class "Default")
      (node (ref "X1") (pin "84") (pinfunction "1_84") (pintype "passive"))
    )
    (net (code "111") (name "unconnected-(X1DA-1-Pad85)") (class "Default")
      (node (ref "X1") (pin "85") (pinfunction "1_85") (pintype "passive"))
    )
    (net (code "112") (name "unconnected-(X1DB-1-Pad86)") (class "Default")
      (node (ref "X1") (pin "86") (pinfunction "1_86") (pintype "passive"))
    )
    (net (code "113") (name "unconnected-(X1DC-1-Pad87)") (class "Default")
      (node (ref "X1") (pin "87") (pinfunction "1_87") (pintype "passive"))
    )
    (net (code "114") (name "unconnected-(X1DD-1-Pad88)") (class "Default")
      (node (ref "X1") (pin "88") (pinfunction "1_88") (pintype "passive"))
    )
    (net (code "115") (name "unconnected-(X2AK-1-Pad23)") (class "Default")
      (node (ref "X2") (pin "23") (pinfunction "1_23") (pintype "passive"))
    )
    (net (code "116") (name "unconnected-(X2AL-1-Pad24)") (class "Default")
      (node (ref "X2") (pin "24") (pinfunction "1_24") (pintype "passive"))
    )
    (net (code "117") (name "unconnected-(X2AM-1-Pad25)") (class "Default")
      (node (ref "X2") (pin "25") (pinfunction "1_25") (pintype "passive"))
    )
    (net (code "118") (name "unconnected-(X2AN-1-Pad26)") (class "Default")
      (node (ref "X2") (pin "26") (pinfunction "1_26") (pintype "passive"))
    )
    (net (code "119") (name "unconnected-(X2AO-1-Pad27)") (class "Default")
      (node (ref "X2") (pin "27") (pinfunction "1_27") (pintype "passive"))
    )
    (net (code "120") (name "unconnected-(X2AP-1-Pad28)") (class "Default")
      (node (ref "X2") (pin "28") (pinfunction "1_28") (pintype "passive"))
    )
    (net (code "121") (name "unconnected-(X2AQ-1-Pad29)") (class "Default")
      (node (ref "X2") (pin "29") (pinfunction "1_29") (pintype "passive"))
    )
    (net (code "122") (name "unconnected-(X2AS-1-Pad30)") (class "Default")
      (node (ref "X2") (pin "30") (pinfunction "1_30") (pintype "passive"))
    )
    (net (code "123") (name "unconnected-(X2AT-1-Pad31)") (class "Default")
      (node (ref "X2") (pin "31") (pinfunction "1_31") (pintype "passive"))
    )
    (net (code "124") (name "unconnected-(X2AU-1-Pad32)") (class "Default")
      (node (ref "X2") (pin "32") (pinfunction "1_32") (pintype "passive"))
    )
    (net (code "125") (name "unconnected-(X2AV-1-Pad33)") (class "Default")
      (node (ref "X2") (pin "33") (pinfunction "1_33") (pintype "passive"))
    )
    (net (code "126") (name "unconnected-(X2AW-1-Pad34)") (class "Default")
      (node (ref "X2") (pin "34") (pinfunction "1_34") (pintype "passive"))
    )
    (net (code "127") (name "unconnected-(X2AX-1-Pad35)") (class "Default")
      (node (ref "X2") (pin "35") (pinfunction "1_35") (pintype "passive"))
    )
    (net (code "128") (name "unconnected-(X2AY-1-Pad36)") (class "Default")
      (node (ref "X2") (pin "36") (pinfunction "1_36") (pintype "passive"))
    )
    (net (code "129") (name "unconnected-(X2AZ-1-Pad37)") (class "Default")
      (node (ref "X2") (pin "37") (pinfunction "1_37") (pintype "passive"))
    )
    (net (code "130") (name "unconnected-(X2BA-1-Pad38)") (class "Default")
      (node (ref "X2") (pin "38") (pinfunction "1_38") (pintype "passive"))
    )
    (net (code "131") (name "unconnected-(X2BB-1-Pad39)") (class "Default")
      (node (ref "X2") (pin "39") (pinfunction "1_39") (pintype "passive"))
    )
    (net (code "132") (name "unconnected-(X2BD-1-Pad40)") (class "Default")
      (node (ref "X2") (pin "40") (pinfunction "1_40") (pintype "passive"))
    )
    (net (code "133") (name "unconnected-(X2BE-1-Pad41)") (class "Default")
      (node (ref "X2") (pin "41") (pinfunction "1_41") (pintype "passive"))
    )
    (net (code "134") (name "unconnected-(X2BF-1-Pad42)") (class "Default")
      (node (ref "X2") (pin "42") (pinfunction "1_42") (pintype "passive"))
    )
    (net (code "135") (name "unconnected-(X2BG-1-Pad43)") (class "Default")
      (node (ref "X2") (pin "43") (pinfunction "1_43") (pintype "passive"))
    )
    (net (code "136") (name "unconnected-(X2BH-1-Pad44)") (class "Default")
      (node (ref "X2") (pin "44") (pinfunction "1_44") (pintype "passive"))
    )
    (net (code "137") (name "unconnected-(X2BI-1-Pad45)") (class "Default")
      (node (ref "X2") (pin "45") (pinfunction "1_45") (pintype "passive"))
    )
    (net (code "138") (name "unconnected-(X2BJ-1-Pad46)") (class "Default")
      (node (ref "X2") (pin "46") (pinfunction "1_46") (pintype "passive"))
    )
    (net (code "139") (name "unconnected-(X2BK-1-Pad47)") (class "Default")
      (node (ref "X2") (pin "47") (pinfunction "1_47") (pintype "passive"))
    )
    (net (code "140") (name "unconnected-(X2BL-1-Pad48)") (class "Default")
      (node (ref "X2") (pin "48") (pinfunction "1_48") (pintype "passive"))
    )
    (net (code "141") (name "unconnected-(X2BM-1-Pad49)") (class "Default")
      (node (ref "X2") (pin "49") (pinfunction "1_49") (pintype "passive"))
    )
    (net (code "142") (name "unconnected-(X2BO-1-Pad50)") (class "Default")
      (node (ref "X2") (pin "50") (pinfunction "1_50") (pintype "passive"))
    )
    (net (code "143") (name "unconnected-(X2BP-1-Pad51)") (class "Default")
      (node (ref "X2") (pin "51") (pinfunction "1_51") (pintype "passive"))
    )
    (net (code "144") (name "unconnected-(X2BQ-1-Pad52)") (class "Default")
      (node (ref "X2") (pin "52") (pinfunction "1_52") (pintype "passive"))
    )
    (net (code "145") (name "unconnected-(X2BR-1-Pad53)") (class "Default")
      (node (ref "X2") (pin "53") (pinfunction "1_53") (pintype "passive"))
    )
    (net (code "146") (name "unconnected-(X2BS-1-Pad54)") (class "Default")
      (node (ref "X2") (pin "54") (pinfunction "1_54") (pintype "passive"))
    )
    (net (code "147") (name "unconnected-(X2BT-1-Pad55)") (class "Default")
      (node (ref "X2") (pin "55") (pinfunction "1_55") (pintype "passive"))
    )
    (net (code "148") (name "unconnected-(X2BU-1-Pad56)") (class "Default")
      (node (ref "X2") (pin "56") (pinfunction "1_56") (pintype "passive"))
    )
    (net (code "149") (name "unconnected-(X2BV-1-Pad57)") (class "Default")
      (node (ref "X2") (pin "57") (pinfunction "1_57") (pintype "passive"))
    )
    (net (code "150") (name "unconnected-(X2BW-1-Pad58)") (class "Default")
      (node (ref "X2") (pin "58") (pinfunction "1_58") (pintype "passive"))
    )
    (net (code "151") (name "unconnected-(X2BX-1-Pad59)") (class "Default")
      (node (ref "X2") (pin "59") (pinfunction "1_59") (pintype "passive"))
    )
    (net (code "152") (name "unconnected-(X2BZ-1-Pad60)") (class "Default")
      (node (ref "X2") (pin "60") (pinfunction "1_60") (pintype "passive"))
    )
    (net (code "153") (name "unconnected-(X2CA-1-Pad61)") (class "Default")
      (node (ref "X2") (pin "61") (pinfunction "1_61") (pintype "passive"))
    )
    (net (code "154") (name "unconnected-(X2CB-1-Pad62)") (class "Default")
      (node (ref "X2") (pin "62") (pinfunction "1_62") (pintype "passive"))
    )
    (net (code "155") (name "unconnected-(X2CC-1-Pad63)") (class "Default")
      (node (ref "X2") (pin "63") (pinfunction "1_63") (pintype "passive"))
    )
    (net (code "156") (name "unconnected-(X2CD-1-Pad64)") (class "Default")
      (node (ref "X2") (pin "64") (pinfunction "1_64") (pintype "passive"))
    )
    (net (code "157") (name "unconnected-(X2CE-1-Pad65)") (class "Default")
      (node (ref "X2") (pin "65") (pinfunction "1_65") (pintype "passive"))
    )
    (net (code "158") (name "unconnected-(X2CF-1-Pad66)") (class "Default")
      (node (ref "X2") (pin "66") (pinfunction "1_66") (pintype "passive"))
    )
    (net (code "159") (name "unconnected-(X2CG-1-Pad67)") (class "Default")
      (node (ref "X2") (pin "67") (pinfunction "1_67") (pintype "passive"))
    )
    (net (code "160") (name "unconnected-(X2CH-1-Pad68)") (class "Default")
      (node (ref "X2") (pin "68") (pinfunction "1_68") (pintype "passive"))
    )
    (net (code "161") (name "unconnected-(X2CI-1-Pad69)") (class "Default")
      (node (ref "X2") (pin "69") (pinfunction "1_69") (pintype "passive"))
    )
    (net (code "162") (name "unconnected-(X2CK-1-Pad70)") (class "Default")
      (node (ref "X2") (pin "70") (pinfunction "1_70") (pintype "passive"))
    )
    (net (code "163") (name "unconnected-(X2CL-1-Pad71)") (class "Default")
      (node (ref "X2") (pin "71") (pinfunction "1_71") (pintype "passive"))
    )
    (net (code "164") (name "unconnected-(X2CM-1-Pad72)") (class "Default")
      (node (ref "X2") (pin "72") (pinfunction "1_72") (pintype "passive"))
    )
    (net (code "165") (name "unconnected-(X2CN-1-Pad73)") (class "Default")
      (node (ref "X2") (pin "73") (pinfunction "1_73") (pintype "passive"))
    )
    (net (code "166") (name "unconnected-(X2CO-1-Pad74)") (class "Default")
      (node (ref "X2") (pin "74") (pinfunction "1_74") (pintype "passive"))
    )
    (net (code "167") (name "unconnected-(X2CP-1-Pad75)") (class "Default")
      (node (ref "X2") (pin "75") (pinfunction "1_75") (pintype "passive"))
    )
    (net (code "168") (name "unconnected-(X2CQ-1-Pad76)") (class "Default")
      (node (ref "X2") (pin "76") (pinfunction "1_76") (pintype "passive"))
    )
    (net (code "169") (name "unconnected-(X2CR-1-Pad77)") (class "Default")
      (node (ref "X2") (pin "77") (pinfunction "1_77") (pintype "passive"))
    )
    (net (code "170") (name "unconnected-(X2CS-1-Pad78)") (class "Default")
      (node (ref "X2") (pin "78") (pinfunction "1_78") (pintype "passive"))
    )
    (net (code "171") (name "unconnected-(X2CT-1-Pad79)") (class "Default")
      (node (ref "X2") (pin "79") (pinfunction "1_79") (pintype "passive"))
    )
    (net (code "172") (name "unconnected-(X2CV-1-Pad80)") (class "Default")
      (node (ref "X2") (pin "80") (pinfunction "1_80") (pintype "passive"))
    )
    (net (code "173") (name "unconnected-(X2CW-1-Pad81)") (class "Default")
      (node (ref "X2") (pin "81") (pinfunction "1_81") (pintype "passive"))
    )
    (net (code "174") (name "unconnected-(X2CX-1-Pad82)") (class "Default")
      (node (ref "X2") (pin "82") (pinfunction "1_82") (pintype "passive"))
    )
    (net (code "175") (name "unconnected-(X2CY-1-Pad83)") (class "Default")
      (node (ref "X2") (pin "83") (pinfunction "1_83") (pintype "passive"))
    )
    (net (code "176") (name "unconnected-(X2CZ-1-Pad84)") (class "Default")
      (node (ref "X2") (pin "84") (pinfunction "1_84") (pintype "passive"))
    )
    (net (code "177") (name "unconnected-(X2DA-1-Pad85)") (class "Default")
      (node (ref "X2") (pin "85") (pinfunction "1_85") (pintype "passive"))
    )
    (net (code "178") (name "unconnected-(X2DB-1-Pad86)") (class "Default")
      (node (ref "X2") (pin "86") (pinfunction "1_86") (pintype "passive"))
    )
    (net (code "179") (name "unconnected-(X2DC-1-Pad87)") (class "Default")
      (node (ref "X2") (pin "87") (pinfunction "1_87") (pintype "passive"))
    )
    (net (code "180") (name "unconnected-(X2DD-1-Pad88)") (class "Default")
      (node (ref "X2") (pin "88") (pinfunction "1_88") (pintype "passive"))
    )
    (net (code "181") (name "unconnected-(X3AK-1-Pad23)") (class "Default")
      (node (ref "X3") (pin "23") (pinfunction "1_23") (pintype "passive"))
    )
    (net (code "182") (name "unconnected-(X3AL-1-Pad24)") (class "Default")
      (node (ref "X3") (pin "24") (pinfunction "1_24") (pintype "passive"))
    )
    (net (code "183") (name "unconnected-(X3AM-1-Pad25)") (class "Default")
      (node (ref "X3") (pin "25") (pinfunction "1_25") (pintype "passive"))
    )
    (net (code "184") (name "unconnected-(X3AN-1-Pad26)") (class "Default")
      (node (ref "X3") (pin "26") (pinfunction "1_26") (pintype "passive"))
    )
    (net (code "185") (name "unconnected-(X3AO-1-Pad27)") (class "Default")
      (node (ref "X3") (pin "27") (pinfunction "1_27") (pintype "passive"))
    )
    (net (code "186") (name "unconnected-(X3AP-1-Pad28)") (class "Default")
      (node (ref "X3") (pin "28") (pinfunction "1_28") (pintype "passive"))
    )
    (net (code "187") (name "unconnected-(X3AQ-1-Pad29)") (class "Default")
      (node (ref "X3") (pin "29") (pinfunction "1_29") (pintype "passive"))
    )
    (net (code "188") (name "unconnected-(X3AS-1-Pad30)") (class "Default")
      (node (ref "X3") (pin "30") (pinfunction "1_30") (pintype "passive"))
    )
    (net (code "189") (name "unconnected-(X3AT-1-Pad31)") (class "Default")
      (node (ref "X3") (pin "31") (pinfunction "1_31") (pintype "passive"))
    )
    (net (code "190") (name "unconnected-(X3AU-1-Pad32)") (class "Default")
      (node (ref "X3") (pin "32") (pinfunction "1_32") (pintype "passive"))
    )
    (net (code "191") (name "unconnected-(X3AV-1-Pad33)") (class "Default")
      (node (ref "X3") (pin "33") (pinfunction "1_33") (pintype "passive"))
    )
    (net (code "192") (name "unconnected-(X3AW-1-Pad34)") (class "Default")
      (node (ref "X3") (pin "34") (pinfunction "1_34") (pintype "passive"))
    )
    (net (code "193") (name "unconnected-(X3AX-1-Pad35)") (class "Default")
      (node (ref "X3") (pin "35") (pinfunction "1_35") (pintype "passive"))
    )
    (net (code "194") (name "unconnected-(X3AY-1-Pad36)") (class "Default")
      (node (ref "X3") (pin "36") (pinfunction "1_36") (pintype "passive"))
    )
    (net (code "195") (name "unconnected-(X3AZ-1-Pad37)") (class "Default")
      (node (ref "X3") (pin "37") (pinfunction "1_37") (pintype "passive"))
    )
    (net (code "196") (name "unconnected-(X3BA-1-Pad38)") (class "Default")
      (node (ref "X3") (pin "38") (pinfunction "1_38") (pintype "passive"))
    )
    (net (code "197") (name "unconnected-(X3BB-1-Pad39)") (class "Default")
      (node (ref "X3") (pin "39") (pinfunction "1_39") (pintype "passive"))
    )
    (net (code "198") (name "unconnected-(X3BD-1-Pad40)") (class "Default")
      (node (ref "X3") (pin "40") (pinfunction "1_40") (pintype "passive"))
    )
    (net (code "199") (name "unconnected-(X3BE-1-Pad41)") (class "Default")
      (node (ref "X3") (pin "41") (pinfunction "1_41") (pintype "passive"))
    )
    (net (code "200") (name "unconnected-(X3BF-1-Pad42)") (class "Default")
      (node (ref "X3") (pin "42") (pinfunction "1_42") (pintype "passive"))
    )
    (net (code "201") (name "unconnected-(X3BG-1-Pad43)") (class "Default")
      (node (ref "X3") (pin "43") (pinfunction "1_43") (pintype "passive"))
    )
    (net (code "202") (name "unconnected-(X3BH-1-Pad44)") (class "Default")
      (node (ref "X3") (pin "44") (pinfunction "1_44") (pintype "passive"))
    )
    (net (code "203") (name "unconnected-(X3BI-1-Pad45)") (class "Default")
      (node (ref "X3") (pin "45") (pinfunction "1_45") (pintype "passive"))
    )
    (net (code "204") (name "unconnected-(X3BJ-1-Pad46)") (class "Default")
      (node (ref "X3") (pin "46") (pinfunction "1_46") (pintype "passive"))
    )
    (net (code "205") (name "unconnected-(X3BK-1-Pad47)") (class "Default")
      (node (ref "X3") (pin "47") (pinfunction "1_47") (pintype "passive"))
    )
    (net (code "206") (name "unconnected-(X3BL-1-Pad48)") (class "Default")
      (node (ref "X3") (pin "48") (pinfunction "1_48") (pintype "passive"))
    )
    (net (code "207") (name "unconnected-(X3BM-1-Pad49)") (class "Default")
      (node (ref "X3") (pin "49") (pinfunction "1_49") (pintype "passive"))
    )
    (net (code "208") (name "unconnected-(X3BO-1-Pad50)") (class "Default")
      (node (ref "X3") (pin "50") (pinfunction "1_50") (pintype "passive"))
    )
    (net (code "209") (name "unconnected-(X3BP-1-Pad51)") (class "Default")
      (node (ref "X3") (pin "51") (pinfunction "1_51") (pintype "passive"))
    )
    (net (code "210") (name "unconnected-(X3BQ-1-Pad52)") (class "Default")
      (node (ref "X3") (pin "52") (pinfunction "1_52") (pintype "passive"))
    )
    (net (code "211") (name "unconnected-(X3BR-1-Pad53)") (class "Default")
      (node (ref "X3") (pin "53") (pinfunction "1_53") (pintype "passive"))
    )
    (net (code "212") (name "unconnected-(X3BS-1-Pad54)") (class "Default")
      (node (ref "X3") (pin "54") (pinfunction "1_54") (pintype "passive"))
    )
    (net (code "213") (name "unconnected-(X3BT-1-Pad55)") (class "Default")
      (node (ref "X3") (pin "55") (pinfunction "1_55") (pintype "passive"))
    )
    (net (code "214") (name "unconnected-(X3BU-1-Pad56)") (class "Default")
      (node (ref "X3") (pin "56") (pinfunction "1_56") (pintype "passive"))
    )
    (net (code "215") (name "unconnected-(X3BV-1-Pad57)") (class "Default")
      (node (ref "X3") (pin "57") (pinfunction "1_57") (pintype "passive"))
    )
    (net (code "216") (name "unconnected-(X3BW-1-Pad58)") (class "Default")
      (node (ref "X3") (pin "58") (pinfunction "1_58") (pintype "passive"))
    )
    (net (code "217") (name "unconnected-(X3BX-1-Pad59)") (class "Default")
      (node (ref "X3") (pin "59") (pinfunction "1_59") (pintype "passive"))
    )
    (net (code "218") (name "unconnected-(X3BZ-1-Pad60)") (class "Default")
      (node (ref "X3") (pin "60") (pinfunction "1_60") (pintype "passive"))
    )
    (net (code "219") (name "unconnected-(X3CA-1-Pad61)") (class "Default")
      (node (ref "X3") (pin "61") (pinfunction "1_61") (pintype "passive"))
    )
    (net (code "220") (name "unconnected-(X3CB-1-Pad62)") (class "Default")
      (node (ref "X3") (pin "62") (pinfunction "1_62") (pintype "passive"))
    )
    (net (code "221") (name "unconnected-(X3CC-1-Pad63)") (class "Default")
      (node (ref "X3") (pin "63") (pinfunction "1_63") (pintype "passive"))
    )
    (net (code "222") (name "unconnected-(X3CD-1-Pad64)") (class "Default")
      (node (ref "X3") (pin "64") (pinfunction "1_64") (pintype "passive"))
    )
    (net (code "223") (name "unconnected-(X3CE-1-Pad65)") (class "Default")
      (node (ref "X3") (pin "65") (pinfunction "1_65") (pintype "passive"))
    )
    (net (code "224") (name "unconnected-(X3CF-1-Pad66)") (class "Default")
      (node (ref "X3") (pin "66") (pinfunction "1_66") (pintype "passive"))
    )
    (net (code "225") (name "unconnected-(X3CG-1-Pad67)") (class "Default")
      (node (ref "X3") (pin "67") (pinfunction "1_67") (pintype "passive"))
    )
    (net (code "226") (name "unconnected-(X3CH-1-Pad68)") (class "Default")
      (node (ref "X3") (pin "68") (pinfunction "1_68") (pintype "passive"))
    )
    (net (code "227") (name "unconnected-(X3CI-1-Pad69)") (class "Default")
      (node (ref "X3") (pin "69") (pinfunction "1_69") (pintype "passive"))
    )
    (net (code "228") (name "unconnected-(X3CK-1-Pad70)") (class "Default")
      (node (ref "X3") (pin "70") (pinfunction "1_70") (pintype "passive"))
    )
    (net (code "229") (name "unconnected-(X3CL-1-Pad71)") (class "Default")
      (node (ref "X3") (pin "71") (pinfunction "1_71") (pintype "passive"))
    )
    (net (code "230") (name "unconnected-(X3CM-1-Pad72)") (class "Default")
      (node (ref "X3") (pin "72") (pinfunction "1_72") (pintype "passive"))
    )
    (net (code "231") (name "unconnected-(X3CN-1-Pad73)") (class "Default")
      (node (ref "X3") (pin "73") (pinfunction "1_73") (pintype "passive"))
    )
    (net (code "232") (name "unconnected-(X3CO-1-Pad74)") (class "Default")
      (node (ref "X3") (pin "74") (pinfunction "1_74") (pintype "passive"))
    )
    (net (code "233") (name "unconnected-(X3CP-1-Pad75)") (class "Default")
      (node (ref "X3") (pin "75") (pinfunction "1_75") (pintype "passive"))
    )
    (net (code "234") (name "unconnected-(X3CQ-1-Pad76)") (class "Default")
      (node (ref "X3") (pin "76") (pinfunction "1_76") (pintype "passive"))
    )
    (net (code "235") (name "unconnected-(X3CR-1-Pad77)") (class "Default")
      (node (ref "X3") (pin "77") (pinfunction "1_77") (pintype "passive"))
    )
    (net (code "236") (name "unconnected-(X3CS-1-Pad78)") (class "Default")
      (node (ref "X3") (pin "78") (pinfunction "1_78") (pintype "passive"))
    )
    (net (code "237") (name "unconnected-(X3CT-1-Pad79)") (class "Default")
      (node (ref "X3") (pin "79") (pinfunction "1_79") (pintype "passive"))
    )
    (net (code "238") (name "unconnected-(X3CV-1-Pad80)") (class "Default")
      (node (ref "X3") (pin "80") (pinfunction "1_80") (pintype "passive"))
    )
    (net (code "239") (name "unconnected-(X3CW-1-Pad81)") (class "Default")
      (node (ref "X3") (pin "81") (pinfunction "1_81") (pintype "passive"))
    )
    (net (code "240") (name "unconnected-(X3CX-1-Pad82)") (class "Default")
      (node (ref "X3") (pin "82") (pinfunction "1_82") (pintype "passive"))
    )
    (net (code "241") (name "unconnected-(X3CY-1-Pad83)") (class "Default")
      (node (ref "X3") (pin "83") (pinfunction "1_83") (pintype "passive"))
    )
    (net (code "242") (name "unconnected-(X3CZ-1-Pad84)") (class "Default")
      (node (ref "X3") (pin "84") (pinfunction "1_84") (pintype "passive"))
    )
    (net (code "243") (name "unconnected-(X3DA-1-Pad85)") (class "Default")
      (node (ref "X3") (pin "85") (pinfunction "1_85") (pintype "passive"))
    )
    (net (code "244") (name "unconnected-(X3DB-1-Pad86)") (class "Default")
      (node (ref "X3") (pin "86") (pinfunction "1_86") (pintype "passive"))
    )
    (net (code "245") (name "unconnected-(X3DC-1-Pad87)") (class "Default")
      (node (ref "X3") (pin "87") (pinfunction "1_87") (pintype "passive"))
    )
    (net (code "246") (name "unconnected-(X3DD-1-Pad88)") (class "Default")
      (node (ref "X3") (pin "88") (pinfunction "1_88") (pintype "passive"))
    )
    (net (code "247") (name "unconnected-(X4AK-1-Pad23)") (class "Default")
      (node (ref "X4") (pin "23") (pinfunction "1_23") (pintype "passive"))
    )
    (net (code "248") (name "unconnected-(X4AL-1-Pad24)") (class "Default")
      (node (ref "X4") (pin "24") (pinfunction "1_24") (pintype "passive"))
    )
    (net (code "249") (name "unconnected-(X4AM-1-Pad25)") (class "Default")
      (node (ref "X4") (pin "25") (pinfunction "1_25") (pintype "passive"))
    )
    (net (code "250") (name "unconnected-(X4AN-1-Pad26)") (class "Default")
      (node (ref "X4") (pin "26") (pinfunction "1_26") (pintype "passive"))
    )
    (net (code "251") (name "unconnected-(X4AO-1-Pad27)") (class "Default")
      (node (ref "X4") (pin "27") (pinfunction "1_27") (pintype "passive"))
    )
    (net (code "252") (name "unconnected-(X4AP-1-Pad28)") (class "Default")
      (node (ref "X4") (pin "28") (pinfunction "1_28") (pintype "passive"))
    )
    (net (code "253") (name "unconnected-(X4AQ-1-Pad29)") (class "Default")
      (node (ref "X4") (pin "29") (pinfunction "1_29") (pintype "passive"))
    )
    (net (code "254") (name "unconnected-(X4AS-1-Pad30)") (class "Default")
      (node (ref "X4") (pin "30") (pinfunction "1_30") (pintype "passive"))
    )
    (net (code "255") (name "unconnected-(X4AT-1-Pad31)") (class "Default")
      (node (ref "X4") (pin "31") (pinfunction "1_31") (pintype "passive"))
    )
    (net (code "256") (name "unconnected-(X4AU-1-Pad32)") (class "Default")
      (node (ref "X4") (pin "32") (pinfunction "1_32") (pintype "passive"))
    )
    (net (code "257") (name "unconnected-(X4AV-1-Pad33)") (class "Default")
      (node (ref "X4") (pin "33") (pinfunction "1_33") (pintype "passive"))
    )
    (net (code "258") (name "unconnected-(X4AW-1-Pad34)") (class "Default")
      (node (ref "X4") (pin "34") (pinfunction "1_34") (pintype "passive"))
    )
    (net (code "259") (name "unconnected-(X4AX-1-Pad35)") (class "Default")
      (node (ref "X4") (pin "35") (pinfunction "1_35") (pintype "passive"))
    )
    (net (code "260") (name "unconnected-(X4AY-1-Pad36)") (class "Default")
      (node (ref "X4") (pin "36") (pinfunction "1_36") (pintype "passive"))
    )
    (net (code "261") (name "unconnected-(X4AZ-1-Pad37)") (class "Default")
      (node (ref "X4") (pin "37") (pinfunction "1_37") (pintype "passive"))
    )
    (net (code "262") (name "unconnected-(X4BA-1-Pad38)") (class "Default")
      (node (ref "X4") (pin "38") (pinfunction "1_38") (pintype "passive"))
    )
    (net (code "263") (name "unconnected-(X4BB-1-Pad39)") (class "Default")
      (node (ref "X4") (pin "39") (pinfunction "1_39") (pintype "passive"))
    )
    (net (code "264") (name "unconnected-(X4BD-1-Pad40)") (class "Default")
      (node (ref "X4") (pin "40") (pinfunction "1_40") (pintype "passive"))
    )
    (net (code "265") (name "unconnected-(X4BE-1-Pad41)") (class "Default")
      (node (ref "X4") (pin "41") (pinfunction "1_41") (pintype "passive"))
    )
    (net (code "266") (name "unconnected-(X4BF-1-Pad42)") (class "Default")
      (node (ref "X4") (pin "42") (pinfunction "1_42") (pintype "passive"))
    )
    (net (code "267") (name "unconnected-(X4BG-1-Pad43)") (class "Default")
      (node (ref "X4") (pin "43") (pinfunction "1_43") (pintype "passive"))
    )
    (net (code "268") (name "unconnected-(X4BH-1-Pad44)") (class "Default")
      (node (ref "X4") (pin "44") (pinfunction "1_44") (pintype "passive"))
    )
    (net (code "269") (name "unconnected-(X4BI-1-Pad45)") (class "Default")
      (node (ref "X4") (pin "45") (pinfunction "1_45") (pintype "passive"))
    )
    (net (code "270") (name "unconnected-(X4BJ-1-Pad46)") (class "Default")
      (node (ref "X4") (pin "46") (pinfunction "1_46") (pintype "passive"))
    )
    (net (code "271") (name "unconnected-(X4BK-1-Pad47)") (class "Default")
      (node (ref "X4") (pin "47") (pinfunction "1_47") (pintype "passive"))
    )
    (net (code "272") (name "unconnected-(X4BL-1-Pad48)") (class "Default")
      (node (ref "X4") (pin "48") (pinfunction "1_48") (pintype "passive"))
    )
    (net (code "273") (name "unconnected-(X4BM-1-Pad49)") (class "Default")
      (node (ref "X4") (pin "49") (pinfunction "1_49") (pintype "passive"))
    )
    (net (code "274") (name "unconnected-(X4BO-1-Pad50)") (class "Default")
      (node (ref "X4") (pin "50") (pinfunction "1_50") (pintype "passive"))
    )
    (net (code "275") (name "unconnected-(X4BP-1-Pad51)") (class "Default")
      (node (ref "X4") (pin "51") (pinfunction "1_51") (pintype "passive"))
    )
    (net (code "276") (name "unconnected-(X4BQ-1-Pad52)") (class "Default")
      (node (ref "X4") (pin "52") (pinfunction "1_52") (pintype "passive"))
    )
    (net (code "277") (name "unconnected-(X4BR-1-Pad53)") (class "Default")
      (node (ref "X4") (pin "53") (pinfunction "1_53") (pintype "passive"))
    )
    (net (code "278") (name "unconnected-(X4BS-1-Pad54)") (class "Default")
      (node (ref "X4") (pin "54") (pinfunction "1_54") (pintype "passive"))
    )
    (net (code "279") (name "unconnected-(X4BT-1-Pad55)") (class "Default")
      (node (ref "X4") (pin "55") (pinfunction "1_55") (pintype "passive"))
    )
    (net (code "280") (name "unconnected-(X4BU-1-Pad56)") (class "Default")
      (node (ref "X4") (pin "56") (pinfunction "1_56") (pintype "passive"))
    )
    (net (code "281") (name "unconnected-(X4BV-1-Pad57)") (class "Default")
      (node (ref "X4") (pin "57") (pinfunction "1_57") (pintype "passive"))
    )
    (net (code "282") (name "unconnected-(X4BW-1-Pad58)") (class "Default")
      (node (ref "X4") (pin "58") (pinfunction "1_58") (pintype "passive"))
    )
    (net (code "283") (name "unconnected-(X4BX-1-Pad59)") (class "Default")
      (node (ref "X4") (pin "59") (pinfunction "1_59") (pintype "passive"))
    )
    (net (code "284") (name "unconnected-(X4BZ-1-Pad60)") (class "Default")
      (node (ref "X4") (pin "60") (pinfunction "1_60") (pintype "passive"))
    )
    (net (code "285") (name "unconnected-(X4CA-1-Pad61)") (class "Default")
      (node (ref "X4") (pin "61") (pinfunction "1_61") (pintype "passive"))
    )
    (net (code "286") (name "unconnected-(X4CB-1-Pad62)") (class "Default")
      (node (ref "X4") (pin "62") (pinfunction "1_62") (pintype "passive"))
    )
    (net (code "287") (name "unconnected-(X4CC-1-Pad63)") (class "Default")
      (node (ref "X4") (pin "63") (pinfunction "1_63") (pintype "passive"))
    )
    (net (code "288") (name "unconnected-(X4CD-1-Pad64)") (class "Default")
      (node (ref "X4") (pin "64") (pinfunction "1_64") (pintype "passive"))
    )
    (net (code "289") (name "unconnected-(X4CE-1-Pad65)") (class "Default")
      (node (ref "X4") (pin "65") (pinfunction "1_65") (pintype "passive"))
    )
    (net (code "290") (name "unconnected-(X4CF-1-Pad66)") (class "Default")
      (node (ref "X4") (pin "66") (pinfunction "1_66") (pintype "passive"))
    )
    (net (code "291") (name "unconnected-(X4CG-1-Pad67)") (class "Default")
      (node (ref "X4") (pin "67") (pinfunction "1_67") (pintype "passive"))
    )
    (net (code "292") (name "unconnected-(X4CH-1-Pad68)") (class "Default")
      (node (ref "X4") (pin "68") (pinfunction "1_68") (pintype "passive"))
    )
    (net (code "293") (name "unconnected-(X4CI-1-Pad69)") (class "Default")
      (node (ref "X4") (pin "69") (pinfunction "1_69") (pintype "passive"))
    )
    (net (code "294") (name "unconnected-(X4CK-1-Pad70)") (class "Default")
      (node (ref "X4") (pin "70") (pinfunction "1_70") (pintype "passive"))
    )
    (net (code "295") (name "unconnected-(X4CL-1-Pad71)") (class "Default")
      (node (ref "X4") (pin "71") (pinfunction "1_71") (pintype "passive"))
    )
    (net (code "296") (name "unconnected-(X4CM-1-Pad72)") (class "Default")
      (node (ref "X4") (pin "72") (pinfunction "1_72") (pintype "passive"))
    )
    (net (code "297") (name "unconnected-(X4CN-1-Pad73)") (class "Default")
      (node (ref "X4") (pin "73") (pinfunction "1_73") (pintype "passive"))
    )
    (net (code "298") (name "unconnected-(X4CO-1-Pad74)") (class "Default")
      (node (ref "X4") (pin "74") (pinfunction "1_74") (pintype "passive"))
    )
    (net (code "299") (name "unconnected-(X4CP-1-Pad75)") (class "Default")
      (node (ref "X4") (pin "75") (pinfunction "1_75") (pintype "passive"))
    )
    (net (code "300") (name "unconnected-(X4CQ-1-Pad76)") (class "Default")
      (node (ref "X4") (pin "76") (pinfunction "1_76") (pintype "passive"))
    )
    (net (code "301") (name "unconnected-(X4CR-1-Pad77)") (class "Default")
      (node (ref "X4") (pin "77") (pinfunction "1_77") (pintype "passive"))
    )
    (net (code "302") (name "unconnected-(X4CS-1-Pad78)") (class "Default")
      (node (ref "X4") (pin "78") (pinfunction "1_78") (pintype "passive"))
    )
    (net (code "303") (name "unconnected-(X4CT-1-Pad79)") (class "Default")
      (node (ref "X4") (pin "79") (pinfunction "1_79") (pintype "passive"))
    )
    (net (code "304") (name "unconnected-(X4CV-1-Pad80)") (class "Default")
      (node (ref "X4") (pin "80") (pinfunction "1_80") (pintype "passive"))
    )
    (net (code "305") (name "unconnected-(X4CW-1-Pad81)") (class "Default")
      (node (ref "X4") (pin "81") (pinfunction "1_81") (pintype "passive"))
    )
    (net (code "306") (name "unconnected-(X4CX-1-Pad82)") (class "Default")
      (node (ref "X4") (pin "82") (pinfunction "1_82") (pintype "passive"))
    )
    (net (code "307") (name "unconnected-(X4CY-1-Pad83)") (class "Default")
      (node (ref "X4") (pin "83") (pinfunction "1_83") (pintype "passive"))
    )
    (net (code "308") (name "unconnected-(X4CZ-1-Pad84)") (class "Default")
      (node (ref "X4") (pin "84") (pinfunction "1_84") (pintype "passive"))
    )
    (net (code "309") (name "unconnected-(X4DA-1-Pad85)") (class "Default")
      (node (ref "X4") (pin "85") (pinfunction "1_85") (pintype "passive"))
    )
    (net (code "310") (name "unconnected-(X4DB-1-Pad86)") (class "Default")
      (node (ref "X4") (pin "86") (pinfunction "1_86") (pintype "passive"))
    )
    (net (code "311") (name "unconnected-(X4DC-1-Pad87)") (class "Default")
      (node (ref "X4") (pin "87") (pinfunction "1_87") (pintype "passive"))
    )
    (net (code "312") (name "unconnected-(X4DD-1-Pad88)") (class "Default")
      (node (ref "X4") (pin "88") (pinfunction "1_88") (pintype "passive"))
    )
  )
)
